# On_Board_Computer.net
KiCad netlist of a schematic drawn in EAGLE
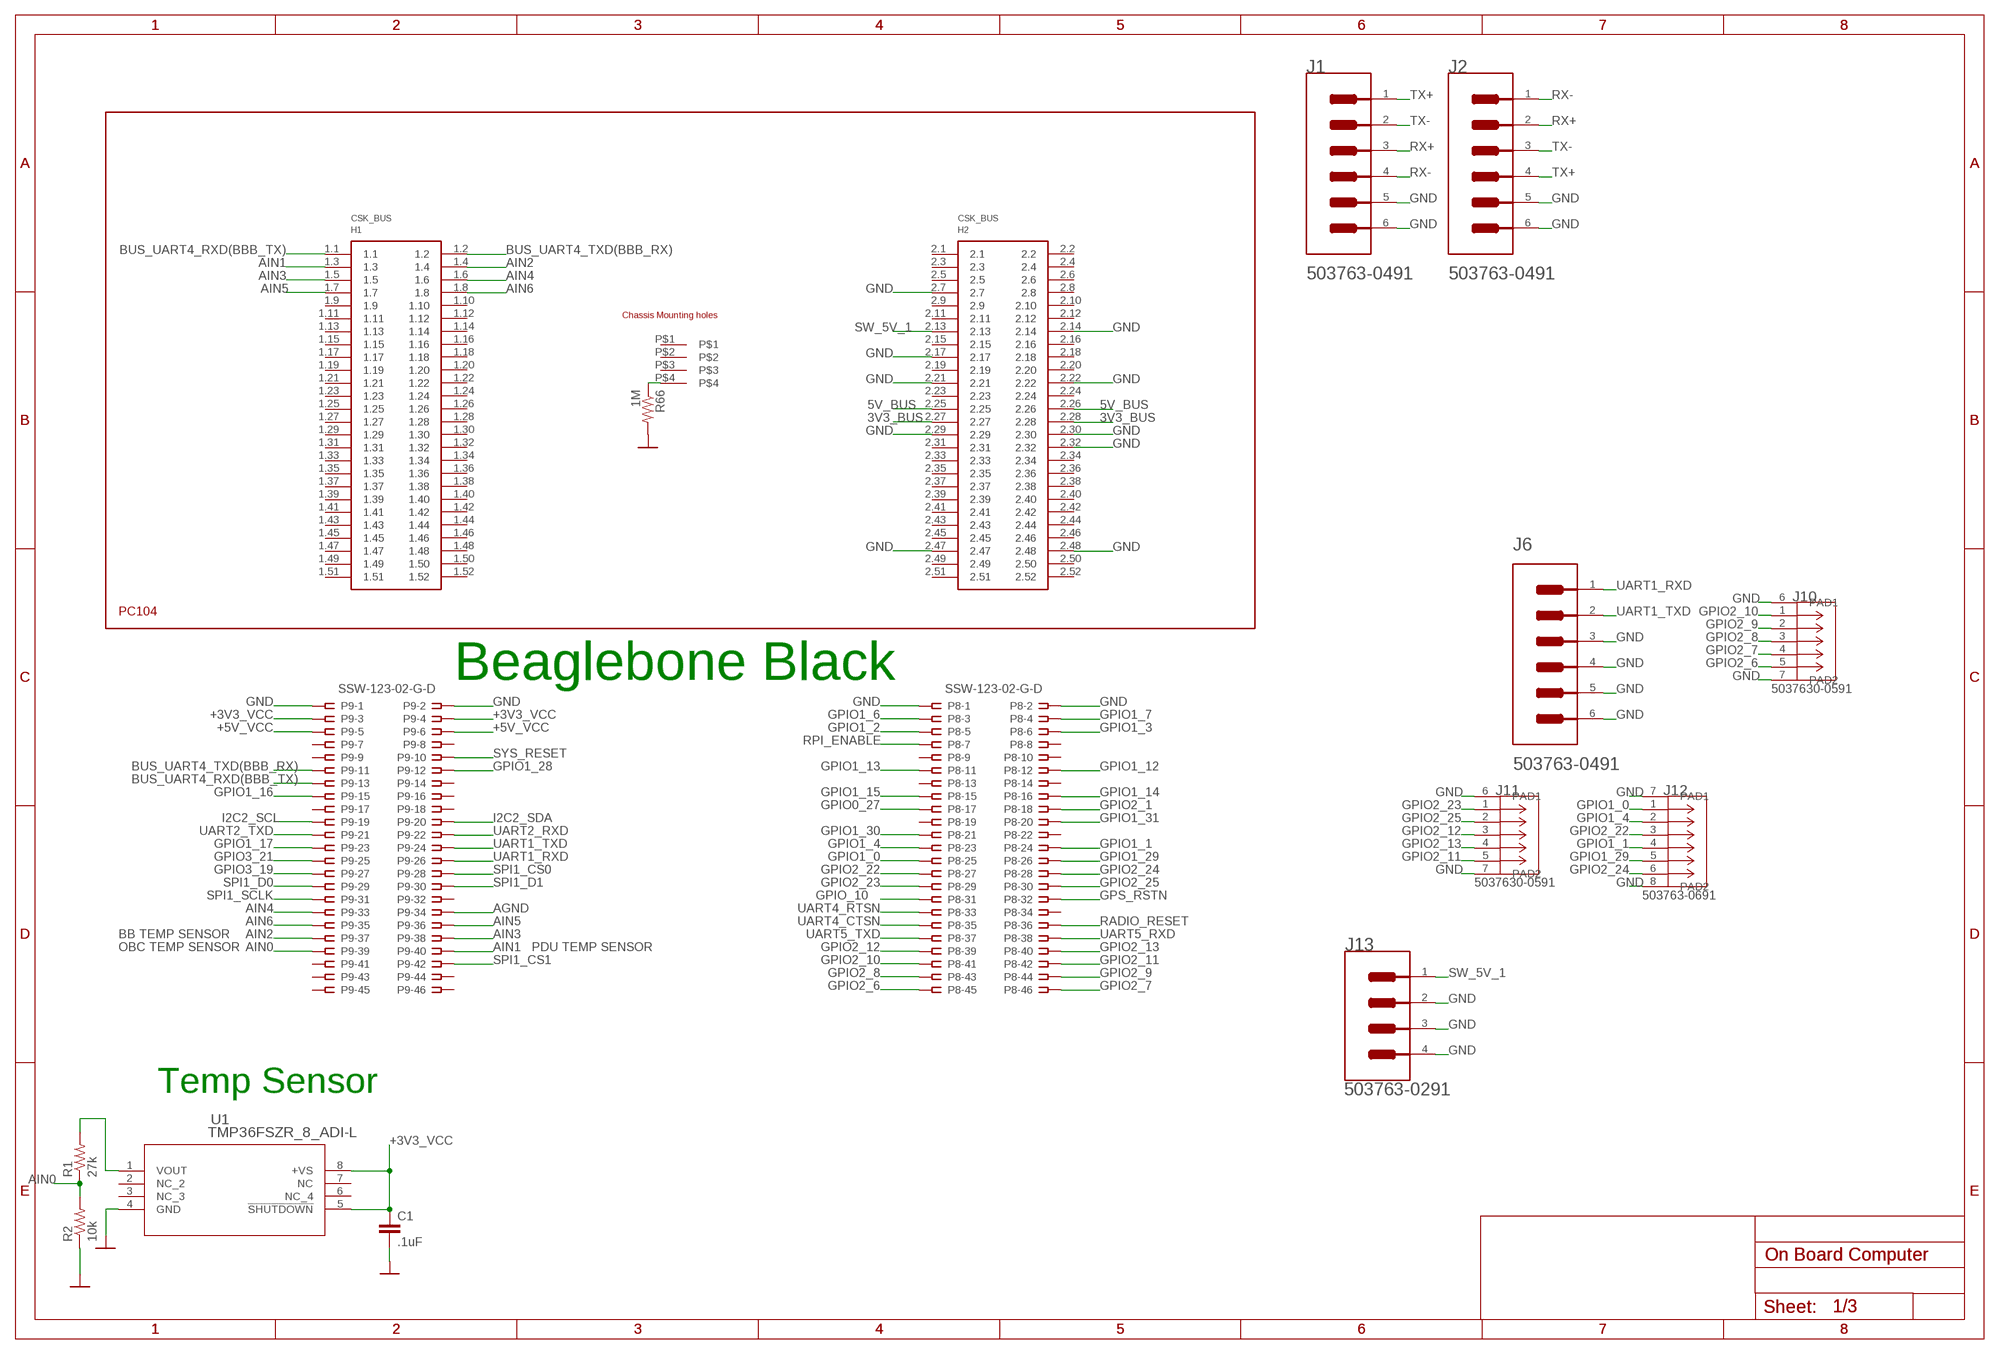
[diagram p0: schematic, sheet 1]
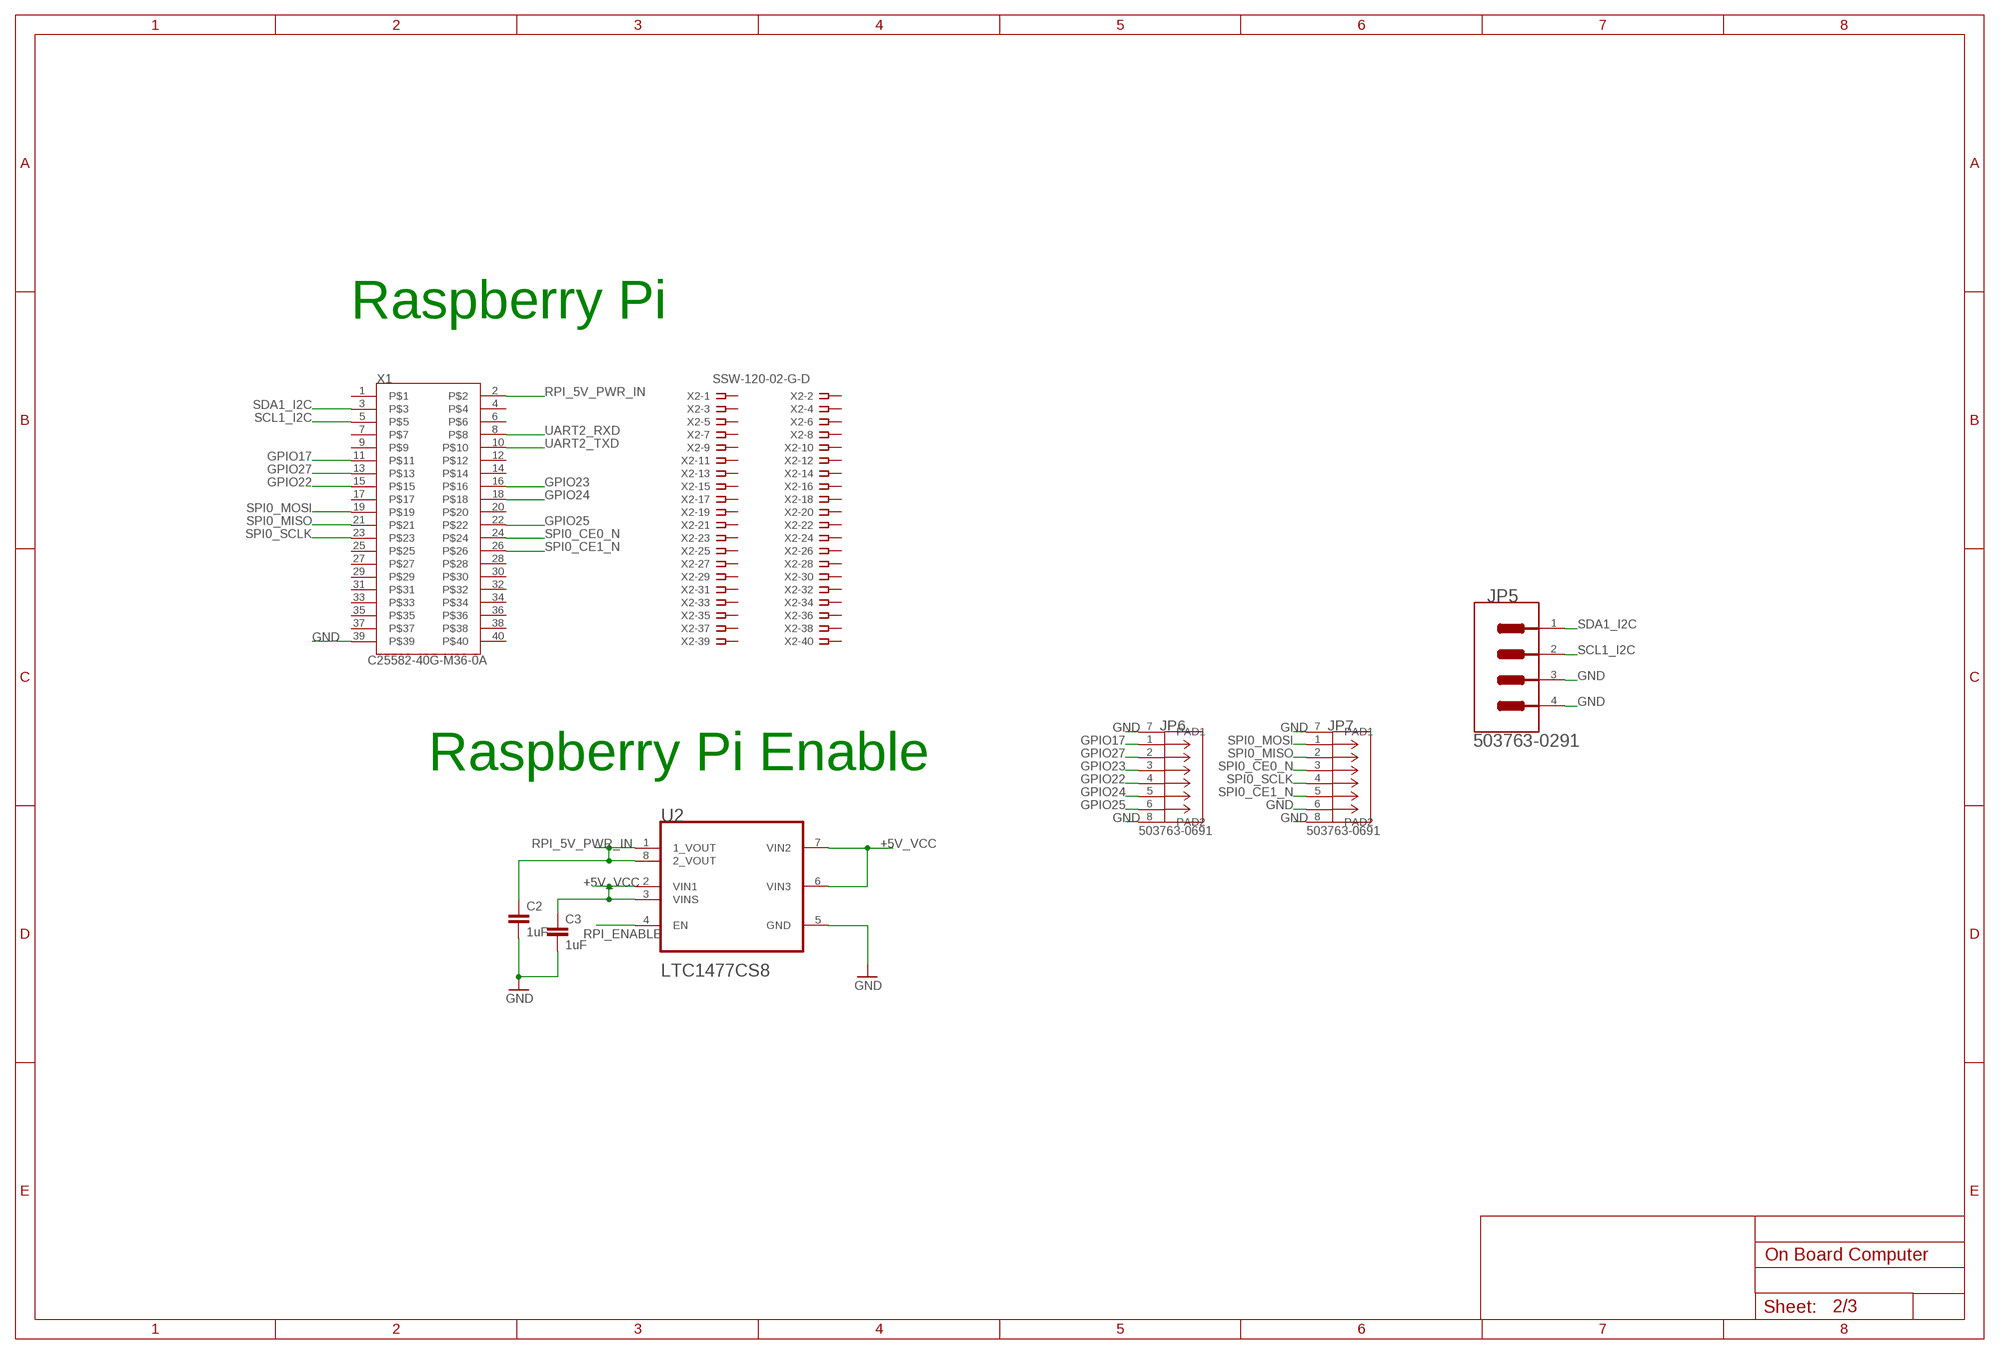
[diagram p1: schematic, sheet 2]
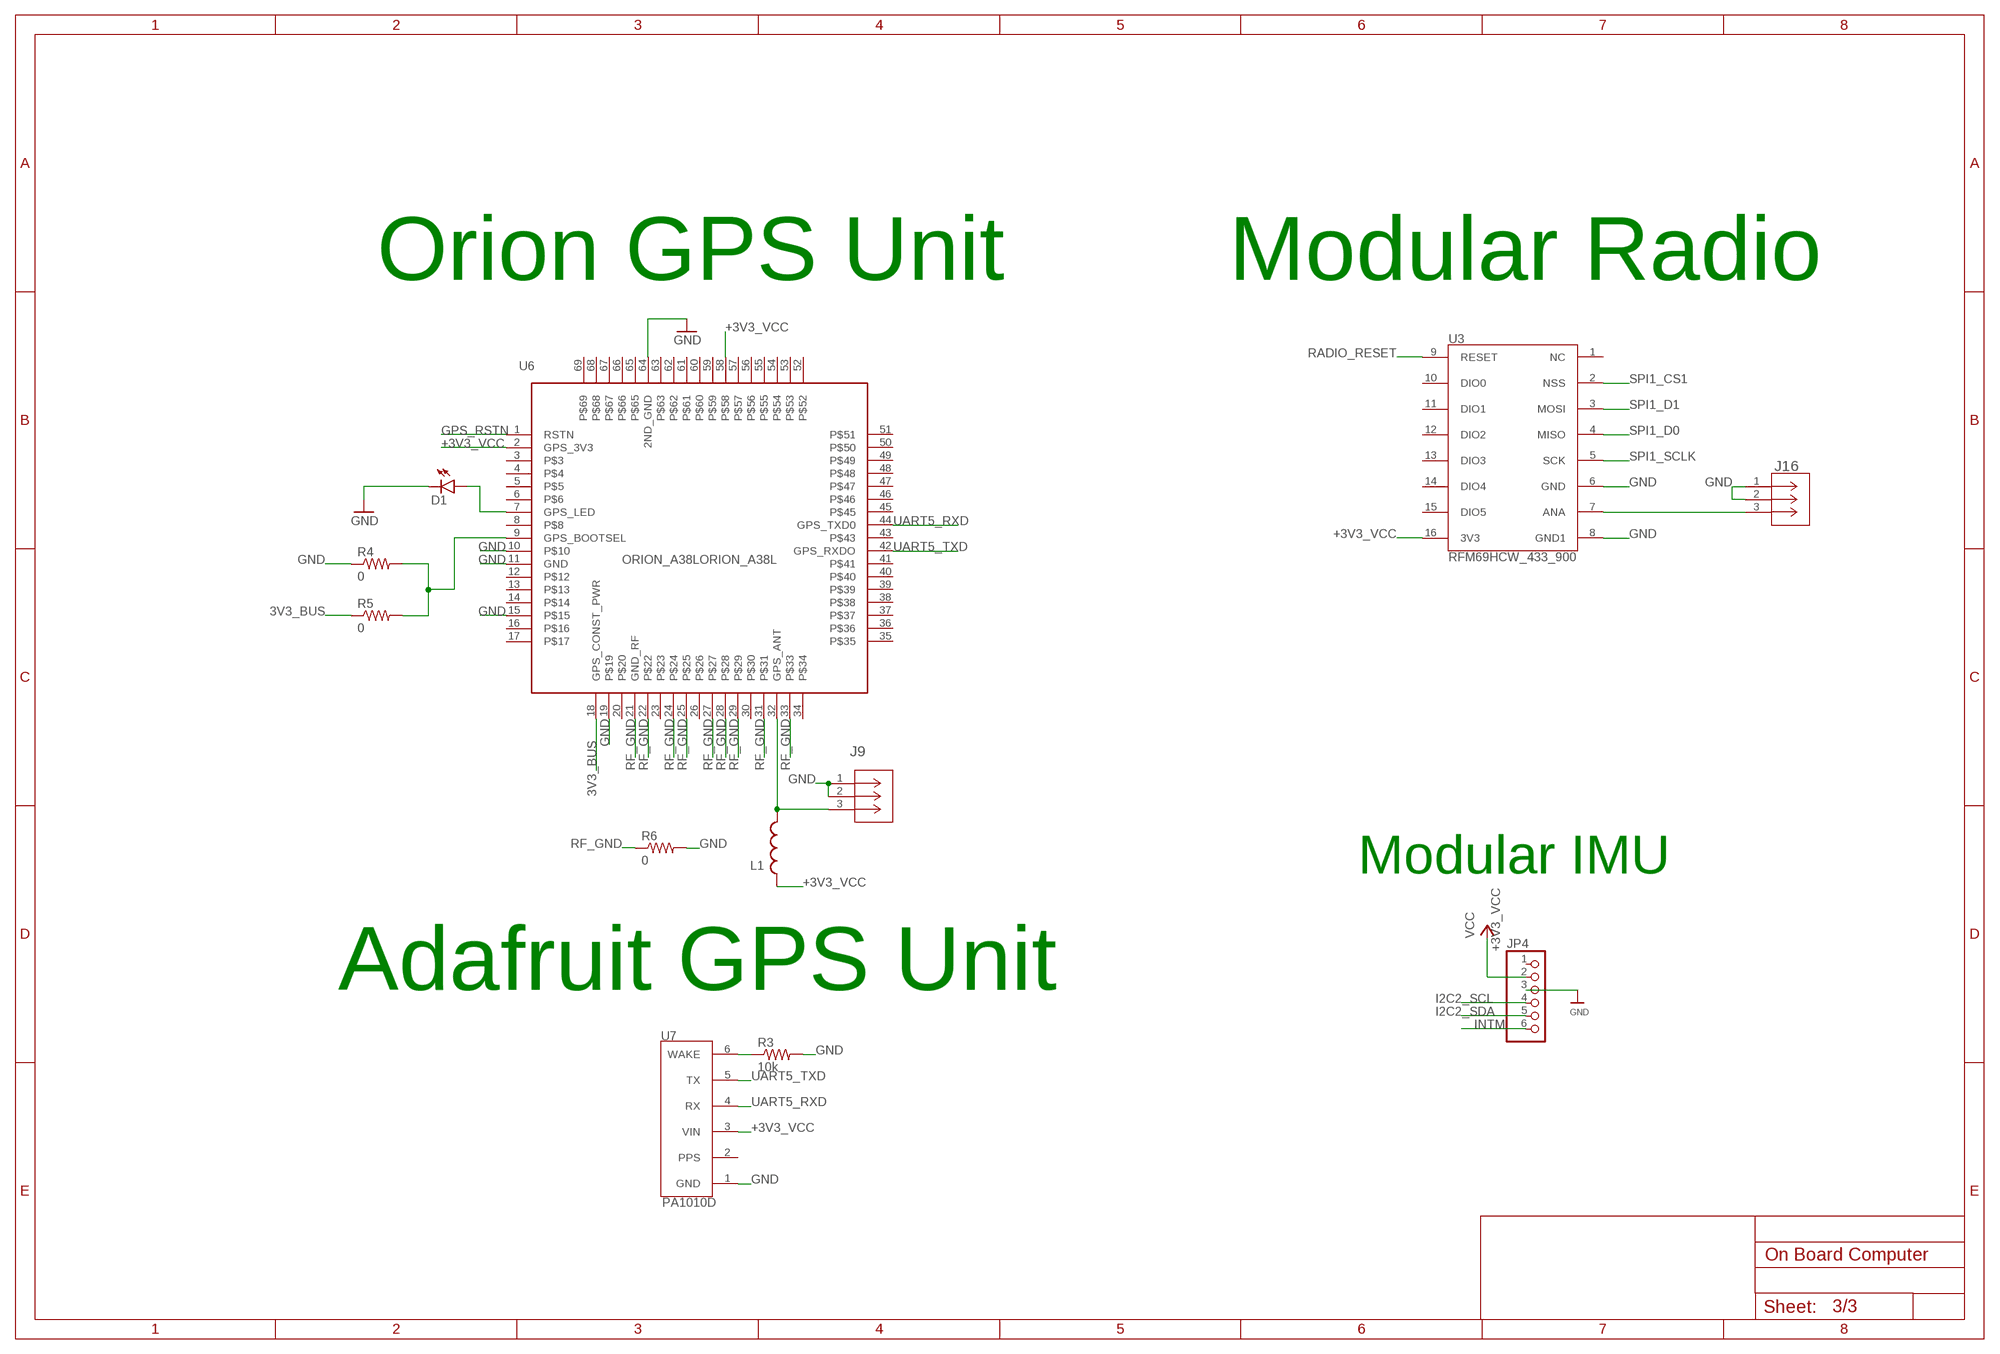
[diagram p2: schematic, sheet 3]

(export (version "E")
  (design (tool "Eeschema 10.0.6"))
  (components
    (comp (ref "D1")
      (value "LEDCHIP-LED0603")
      (footprint "eagle-import:CHIP-LED0603")
      (libsource (lib "eagle-import") (part "LEDCHIP-LED0603"))
    )
    (comp (ref "J9")
      (value "U.FL-R-SMT-1(01)")
      (footprint "eagle-import:CONN_-SMT-1(01)")
      (fields (field (name "COPYRIGHT") "Copyright (C) 2018 Accelerated Designs. All rights reserved"))
      (libsource (lib "eagle-import") (part "U.FL-R-SMT-1(01)"))
    )
    (comp (ref "J16")
      (value "U.FL-R-SMT-1(01)")
      (footprint "eagle-import:CONN_-SMT-1(01)")
      (fields (field (name "COPYRIGHT") "Copyright (C) 2018 Accelerated Designs. All rights reserved"))
      (libsource (lib "eagle-import") (part "U.FL-R-SMT-1(01)"))
    )
    (comp (ref "JP4")
      (value "HEADER-1X670MIL")
      (footprint "eagle-import:1X06_ROUND_70")
      (libsource (lib "eagle-import") (part "HEADER-1X670MIL"))
    )
    (comp (ref "L1")
      (value "L")
      (footprint "eagle-import:INDC2012X145N")
      (fields
        (field (name "DIGI-KEY_PART_NUMBER") "490-18463-1-ND")
        (field (name "MF") "Murata Electronics North America")
        (field (name "MP") "LQM21DH100M70L")
      )
      (libsource (lib "eagle-import") (part "L"))
    )
    (comp (ref "R3")
      (value "10k")
      (footprint "eagle-import:0805")
      (libsource (lib "eagle-import") (part "RESISTOR0805-RES"))
    )
    (comp (ref "R4")
      (value "0")
      (footprint "eagle-import:0805")
      (libsource (lib "eagle-import") (part "RESISTOR0805-RES"))
    )
    (comp (ref "R5")
      (value "0")
      (footprint "eagle-import:0805")
      (libsource (lib "eagle-import") (part "RESISTOR0805-RES"))
    )
    (comp (ref "R6")
      (value "0")
      (footprint "eagle-import:0805")
      (libsource (lib "eagle-import") (part "RESISTOR0805-RES"))
    )
    (comp (ref "U3")
      (value "RFM69HCW_433_900")
      (footprint "eagle-import:RFM69HCW_433")
      (libsource (lib "eagle-import") (part "RFM69HCW_433_900"))
    )
    (comp (ref "U6")
      (value "ORION_A38LORION_A38L")
      (footprint "eagle-import:ORION_A38L")
      (libsource (lib "eagle-import") (part "ORION_A38LORION_A38L"))
    )
    (comp (ref "U7")
      (value "PA1010D")
      (footprint "eagle-import:PA1010D")
      (libsource (lib "eagle-import") (part "PA1010D"))
    )
    (comp (ref "C2")
      (value "1uF")
      (footprint "eagle-import:0805")
      (libsource (lib "eagle-import") (part "CAP0805"))
    )
    (comp (ref "C3")
      (value "1uF")
      (footprint "eagle-import:0805")
      (libsource (lib "eagle-import") (part "CAP0805"))
    )
    (comp (ref "JP5")
      (value "MOLEX_503763-0291MOLEX_503763-0291_0_0")
      (footprint "eagle-import:MOLEX_503763-0291_0")
      (fields
        (field (name "DIGIKEY_PART_NUMBER") "WM10654CT-ND")
        (field (name "MF") "Molex")
        (field (name "MOUSER_PART_NUMBER") "538-503763-0291")
      )
      (libsource (lib "eagle-import") (part "MOLEX_503763-0291MOLEX_503763-0291_0_0"))
    )
    (comp (ref "JP6")
      (value "503763-0691")
      (footprint "eagle-import:CONN_503763-0691_MOL")
      (fields (field (name "COPYRIGHT") "Copyright (C) 2018 Accelerated Designs. All rights reserved"))
      (libsource (lib "eagle-import") (part "503763-0691"))
    )
    (comp (ref "JP7")
      (value "503763-0691")
      (footprint "eagle-import:CONN_503763-0691_MOL")
      (fields (field (name "COPYRIGHT") "Copyright (C) 2018 Accelerated Designs. All rights reserved"))
      (libsource (lib "eagle-import") (part "503763-0691"))
    )
    (comp (ref "U2")
      (value "LTC1477CS8LINEAR_TECHNOLOGY_LTC1477CS8_0_2")
      (footprint "eagle-import:LINEAR_TECHNOLOGY_LTC1477CS8_2")
      (fields (field (name "MF") "Linear Technology") (field (name "MPN") "LTC1477CS8"))
      (libsource (lib "eagle-import") (part "LTC1477CS8LINEAR_TECHNOLOGY_LTC1477CS8_0_2"))
    )
    (comp (ref "X1")
      (value "C25582-40G-M36-0A")
      (footprint "eagle-import:ADAFRUIT_C25582-40G-M36-0A_0")
      (libsource (lib "eagle-import") (part "C25582-40G-M36-0A"))
    )
    (comp (ref "X2")
      (value "SSW-120-02-G-D")
      (footprint "eagle-import:SSW-120-02-G-D")
      (fields (field (name "MF") "Samtec Inc."))
      (libsource (lib "eagle-import") (part "SSW-120-02-G-D"))
    )
    (comp (ref "C1")
      (value ".1uF")
      (footprint "eagle-import:0805")
      (libsource (lib "eagle-import") (part "CAP0805"))
    )
    (comp (ref "H1")
      (value "PC104_WCONN")
      (footprint "eagle-import:PC104_WCONN")
      (libsource (lib "eagle-import") (part "PC104_WCONN"))
    )
    (comp (ref "J1")
      (value "MOLEX_503763-0491MOLEX_503763-0491_0_0")
      (footprint "eagle-import:MOLEX_503763-0491_0")
      (fields
        (field (name "DIGIKEY_PART_NUMBER") "WM10655CT-ND")
        (field (name "MF") "Molex")
        (field (name "MOUSER_PART_NUMBER") "538-503763-0491")
      )
      (libsource (lib "eagle-import") (part "MOLEX_503763-0491MOLEX_503763-0491_0_0"))
    )
    (comp (ref "J2")
      (value "MOLEX_503763-0491MOLEX_503763-0491_0_0")
      (footprint "eagle-import:MOLEX_503763-0491_0")
      (fields
        (field (name "DIGIKEY_PART_NUMBER") "WM10655CT-ND")
        (field (name "MF") "Molex")
        (field (name "MOUSER_PART_NUMBER") "538-503763-0491")
      )
      (libsource (lib "eagle-import") (part "MOLEX_503763-0491MOLEX_503763-0491_0_0"))
    )
    (comp (ref "J6")
      (value "MOLEX_503763-0491MOLEX_503763-0491_0_0")
      (footprint "eagle-import:MOLEX_503763-0491_0")
      (fields
        (field (name "DIGIKEY_PART_NUMBER") "WM10655CT-ND")
        (field (name "MF") "Molex")
        (field (name "MOUSER_PART_NUMBER") "538-503763-0491")
      )
      (libsource (lib "eagle-import") (part "MOLEX_503763-0491MOLEX_503763-0491_0_0"))
    )
    (comp (ref "J10")
      (value "503763-0591")
      (footprint "eagle-import:CONN_5037630591_MOL")
      (fields (field (name "COPYRIGHT") "Copyright (C) 2018 Accelerated Designs. All rights reserved"))
      (libsource (lib "eagle-import") (part "503763-0591"))
    )
    (comp (ref "J11")
      (value "503763-0591")
      (footprint "eagle-import:CONN_5037630591_MOL")
      (fields (field (name "COPYRIGHT") "Copyright (C) 2018 Accelerated Designs. All rights reserved"))
      (libsource (lib "eagle-import") (part "503763-0591"))
    )
    (comp (ref "J12")
      (value "503763-0691")
      (footprint "eagle-import:CONN_503763-0691_MOL")
      (fields (field (name "COPYRIGHT") "Copyright (C) 2018 Accelerated Designs. All rights reserved"))
      (libsource (lib "eagle-import") (part "503763-0691"))
    )
    (comp (ref "J13")
      (value "MOLEX_503763-0291MOLEX_503763-0291_0_0")
      (footprint "eagle-import:MOLEX_503763-0291_0")
      (fields
        (field (name "DIGIKEY_PART_NUMBER") "WM10654CT-ND")
        (field (name "MF") "Molex")
        (field (name "MOUSER_PART_NUMBER") "538-503763-0291")
      )
      (libsource (lib "eagle-import") (part "MOLEX_503763-0291MOLEX_503763-0291_0_0"))
    )
    (comp (ref "P8")
      (value "SSW-123-02-G-D")
      (footprint "eagle-import:SSW-123-02-G-D")
      (fields (field (name "MF") "Samtec Inc."))
      (libsource (lib "eagle-import") (part "SSW-123-02-G-D"))
    )
    (comp (ref "P9")
      (value "SSW-123-02-G-D")
      (footprint "eagle-import:SSW-123-02-G-D")
      (fields (field (name "MF") "Samtec Inc."))
      (libsource (lib "eagle-import") (part "SSW-123-02-G-D"))
    )
    (comp (ref "R1")
      (value "27k")
      (footprint "eagle-import:0805")
      (libsource (lib "eagle-import") (part "RESISTOR0805-RES"))
    )
    (comp (ref "R2")
      (value "10k")
      (footprint "eagle-import:0805")
      (libsource (lib "eagle-import") (part "RESISTOR0805-RES"))
    )
    (comp (ref "R66")
      (value "1M")
      (footprint "eagle-import:0805")
      (libsource (lib "eagle-import") (part "RESISTOR0805-RES"))
    )
    (comp (ref "U1")
      (value "TMP36FSZR_8_ADI-L")
      (footprint "eagle-import:R_8_ADI-L")
      (fields
        (field (name "MANUFACTURER_PART_NUMBER") "TMP36FSZ")
        (field (name "COPYRIGHT") "Copyright (C) 2021 Ultra Librarian. All rights reserved.")
      )
      (libsource (lib "eagle-import") (part "TMP36FSZR_8_ADI-L"))
    )
  )
  (nets
    (net (code "1") (name "+3V3_VCC") (class "Default")
      (node (ref "C1") (pin "1") (pinfunction "1_1") (pintype "passive"))
      (node (ref "JP4") (pin "2") (pinfunction "2_2") (pintype "passive"))
      (node (ref "L1") (pin "1") (pinfunction "1_1") (pintype "passive"))
      (node (ref "P9") (pin "3") (pinfunction "1_3") (pintype "passive"))
      (node (ref "P9") (pin "4") (pinfunction "1_4") (pintype "passive"))
      (node (ref "U1") (pin "5") (pinfunction "~{SHUTDOWN}_5") (pintype "passive"))
      (node (ref "U1") (pin "8") (pinfunction "+VS_8") (pintype "power_in"))
      (node (ref "U3") (pin "16") (pinfunction "3V3_16") (pintype "bidirectional"))
      (node (ref "U6") (pin "2") (pinfunction "GPS_3V3_2") (pintype "bidirectional"))
      (node (ref "U6") (pin "58") (pinfunction "P$58_58") (pintype "bidirectional"))
      (node (ref "U7") (pin "3") (pinfunction "VIN_3") (pintype "bidirectional"))
    )
    (net (code "2") (name "+5V_VCC") (class "Default")
      (node (ref "C3") (pin "1") (pinfunction "1_1") (pintype "passive"))
      (node (ref "P9") (pin "5") (pinfunction "1_5") (pintype "passive"))
      (node (ref "P9") (pin "6") (pinfunction "1_6") (pintype "passive"))
      (node (ref "U2") (pin "2") (pinfunction "VIN1_2") (pintype "power_in"))
      (node (ref "U2") (pin "3") (pinfunction "VINS_3") (pintype "power_in"))
      (node (ref "U2") (pin "6") (pinfunction "VIN3_6") (pintype "power_in"))
      (node (ref "U2") (pin "7") (pinfunction "VIN2_7") (pintype "power_in"))
    )
    (net (code "3") (name "3V3_BUS") (class "Default")
      (node (ref "H1") (pin "2.27") (pinfunction "2.27_2.27") (pintype "bidirectional"))
      (node (ref "H1") (pin "2.28") (pinfunction "2.28_2.28") (pintype "bidirectional"))
      (node (ref "R5") (pin "1") (pinfunction "1_1") (pintype "passive"))
      (node (ref "U6") (pin "18") (pinfunction "GPS_CONST_PWR_18") (pintype "bidirectional"))
    )
    (net (code "4") (name "5V_BUS") (class "Default")
      (node (ref "H1") (pin "2.25") (pinfunction "2.25_2.25") (pintype "bidirectional"))
      (node (ref "H1") (pin "2.26") (pinfunction "2.26_2.26") (pintype "bidirectional"))
    )
    (net (code "5") (name "AGND") (class "Default")
      (node (ref "P9") (pin "34") (pinfunction "1_34") (pintype "passive"))
    )
    (net (code "6") (name "AIN0") (class "Default")
      (node (ref "P9") (pin "39") (pinfunction "1_39") (pintype "passive"))
      (node (ref "R1") (pin "1") (pinfunction "1_1") (pintype "passive"))
      (node (ref "R2") (pin "2") (pinfunction "2_2") (pintype "passive"))
    )
    (net (code "7") (name "AIN1") (class "Default")
      (node (ref "H1") (pin "1.3") (pinfunction "1.3_1.3") (pintype "bidirectional"))
      (node (ref "P9") (pin "40") (pinfunction "1_40") (pintype "passive"))
    )
    (net (code "8") (name "AIN2") (class "Default")
      (node (ref "H1") (pin "1.4") (pinfunction "1.4_1.4") (pintype "bidirectional"))
      (node (ref "P9") (pin "37") (pinfunction "1_37") (pintype "passive"))
    )
    (net (code "9") (name "AIN3") (class "Default")
      (node (ref "H1") (pin "1.5") (pinfunction "1.5_1.5") (pintype "bidirectional"))
      (node (ref "P9") (pin "38") (pinfunction "1_38") (pintype "passive"))
    )
    (net (code "10") (name "AIN4") (class "Default")
      (node (ref "H1") (pin "1.6") (pinfunction "1.6_1.6") (pintype "bidirectional"))
      (node (ref "P9") (pin "33") (pinfunction "1_33") (pintype "passive"))
    )
    (net (code "11") (name "AIN5") (class "Default")
      (node (ref "H1") (pin "1.7") (pinfunction "1.7_1.7") (pintype "bidirectional"))
      (node (ref "P9") (pin "36") (pinfunction "1_36") (pintype "passive"))
    )
    (net (code "12") (name "AIN6") (class "Default")
      (node (ref "H1") (pin "1.8") (pinfunction "1.8_1.8") (pintype "bidirectional"))
      (node (ref "P9") (pin "35") (pinfunction "1_35") (pintype "passive"))
    )
    (net (code "13") (name "BUS_UART4_RXD(BBB_TX)") (class "Default")
      (node (ref "H1") (pin "1.1") (pinfunction "1.1_1.1") (pintype "bidirectional"))
      (node (ref "P9") (pin "13") (pinfunction "1_13") (pintype "passive"))
    )
    (net (code "14") (name "BUS_UART4_TXD(BBB_RX)") (class "Default")
      (node (ref "H1") (pin "1.2") (pinfunction "1.2_1.2") (pintype "bidirectional"))
      (node (ref "P9") (pin "11") (pinfunction "1_11") (pintype "passive"))
    )
    (net (code "15") (name "GND") (class "Default")
      (node (ref "C1") (pin "2") (pinfunction "2_2") (pintype "passive"))
      (node (ref "C2") (pin "2") (pinfunction "2_2") (pintype "passive"))
      (node (ref "C3") (pin "2") (pinfunction "2_2") (pintype "passive"))
      (node (ref "D1") (pin "C") (pinfunction "C_C") (pintype "passive"))
      (node (ref "H1") (pin "2.14") (pinfunction "2.14_2.14") (pintype "bidirectional"))
      (node (ref "H1") (pin "2.17") (pinfunction "2.17_2.17") (pintype "bidirectional"))
      (node (ref "H1") (pin "2.21") (pinfunction "2.21_2.21") (pintype "bidirectional"))
      (node (ref "H1") (pin "2.22") (pinfunction "2.22_2.22") (pintype "bidirectional"))
      (node (ref "H1") (pin "2.29") (pinfunction "2.29_2.29") (pintype "bidirectional"))
      (node (ref "H1") (pin "2.30") (pinfunction "2.30_2.30") (pintype "bidirectional"))
      (node (ref "H1") (pin "2.32") (pinfunction "2.32_2.32") (pintype "bidirectional"))
      (node (ref "H1") (pin "2.47") (pinfunction "2.47_2.47") (pintype "bidirectional"))
      (node (ref "H1") (pin "2.48") (pinfunction "2.48_2.48") (pintype "bidirectional"))
      (node (ref "H1") (pin "2.7") (pinfunction "2.7_2.7") (pintype "bidirectional"))
      (node (ref "J1") (pin "5") (pinfunction "MNT_1_5") (pintype "passive"))
      (node (ref "J1") (pin "6") (pinfunction "MNT_2_6") (pintype "passive"))
      (node (ref "J10") (pin "6") (pinfunction "PAD1_6") (pintype "bidirectional"))
      (node (ref "J10") (pin "7") (pinfunction "PAD2_7") (pintype "bidirectional"))
      (node (ref "J11") (pin "6") (pinfunction "PAD1_6") (pintype "bidirectional"))
      (node (ref "J11") (pin "7") (pinfunction "PAD2_7") (pintype "bidirectional"))
      (node (ref "J12") (pin "7") (pinfunction "PAD1_7") (pintype "bidirectional"))
      (node (ref "J12") (pin "8") (pinfunction "PAD2_8") (pintype "bidirectional"))
      (node (ref "J13") (pin "2") (pinfunction "2_2") (pintype "bidirectional"))
      (node (ref "J13") (pin "3") (pinfunction "MNT_1_3") (pintype "bidirectional"))
      (node (ref "J13") (pin "4") (pinfunction "MNT_2_4") (pintype "bidirectional"))
      (node (ref "J16") (pin "1") (pinfunction "1_1") (pintype "passive"))
      (node (ref "J16") (pin "2") (pinfunction "2_2") (pintype "passive"))
      (node (ref "J2") (pin "5") (pinfunction "MNT_1_5") (pintype "passive"))
      (node (ref "J2") (pin "6") (pinfunction "MNT_2_6") (pintype "passive"))
      (node (ref "J6") (pin "3") (pinfunction "3_3") (pintype "passive"))
      (node (ref "J6") (pin "4") (pinfunction "4_4") (pintype "passive"))
      (node (ref "J6") (pin "5") (pinfunction "MNT_1_5") (pintype "passive"))
      (node (ref "J6") (pin "6") (pinfunction "MNT_2_6") (pintype "passive"))
      (node (ref "J9") (pin "1") (pinfunction "1_1") (pintype "passive"))
      (node (ref "J9") (pin "2") (pinfunction "2_2") (pintype "passive"))
      (node (ref "JP4") (pin "3") (pinfunction "3_3") (pintype "passive"))
      (node (ref "JP5") (pin "3") (pinfunction "MNT_1_3") (pintype "bidirectional"))
      (node (ref "JP5") (pin "4") (pinfunction "MNT_2_4") (pintype "bidirectional"))
      (node (ref "JP6") (pin "7") (pinfunction "PAD1_7") (pintype "bidirectional"))
      (node (ref "JP6") (pin "8") (pinfunction "PAD2_8") (pintype "bidirectional"))
      (node (ref "JP7") (pin "6") (pinfunction "6_6") (pintype "passive"))
      (node (ref "JP7") (pin "7") (pinfunction "PAD1_7") (pintype "bidirectional"))
      (node (ref "JP7") (pin "8") (pinfunction "PAD2_8") (pintype "bidirectional"))
      (node (ref "P8") (pin "1") (pinfunction "1_1") (pintype "passive"))
      (node (ref "P8") (pin "2") (pinfunction "1_2") (pintype "passive"))
      (node (ref "P9") (pin "1") (pinfunction "1_1") (pintype "passive"))
      (node (ref "P9") (pin "2") (pinfunction "1_2") (pintype "passive"))
      (node (ref "R2") (pin "1") (pinfunction "1_1") (pintype "passive"))
      (node (ref "R3") (pin "2") (pinfunction "2_2") (pintype "passive"))
      (node (ref "R4") (pin "1") (pinfunction "1_1") (pintype "passive"))
      (node (ref "R6") (pin "2") (pinfunction "2_2") (pintype "passive"))
      (node (ref "R66") (pin "2") (pinfunction "2_2") (pintype "passive"))
      (node (ref "U1") (pin "4") (pinfunction "GND_4") (pintype "passive"))
      (node (ref "U2") (pin "5") (pinfunction "GND_5") (pintype "power_in"))
      (node (ref "U3") (pin "6") (pinfunction "GND_6") (pintype "bidirectional"))
      (node (ref "U3") (pin "8") (pinfunction "GND1_8") (pintype "bidirectional"))
      (node (ref "U6") (pin "10") (pinfunction "P$10_10") (pintype "bidirectional"))
      (node (ref "U6") (pin "11") (pinfunction "GND_11") (pintype "bidirectional"))
      (node (ref "U6") (pin "15") (pinfunction "P$15_15") (pintype "bidirectional"))
      (node (ref "U6") (pin "19") (pinfunction "P$19_19") (pintype "bidirectional"))
      (node (ref "U6") (pin "64") (pinfunction "2ND_GND_64") (pintype "bidirectional"))
      (node (ref "U7") (pin "1") (pinfunction "GND_1") (pintype "bidirectional"))
      (node (ref "X1") (pin "39") (pinfunction "P$39_39") (pintype "bidirectional"))
    )
    (net (code "16") (name "GPIO0_27") (class "Default")
      (node (ref "P8") (pin "17") (pinfunction "1_17") (pintype "passive"))
    )
    (net (code "17") (name "GPIO1_0") (class "Default")
      (node (ref "J12") (pin "1") (pinfunction "1_1") (pintype "passive"))
      (node (ref "P8") (pin "25") (pinfunction "1_25") (pintype "passive"))
    )
    (net (code "18") (name "GPIO1_1") (class "Default")
      (node (ref "J12") (pin "4") (pinfunction "4_4") (pintype "passive"))
      (node (ref "P8") (pin "24") (pinfunction "1_24") (pintype "passive"))
    )
    (net (code "19") (name "GPIO1_2") (class "Default")
      (node (ref "P8") (pin "5") (pinfunction "1_5") (pintype "passive"))
    )
    (net (code "20") (name "GPIO1_3") (class "Default")
      (node (ref "P8") (pin "6") (pinfunction "1_6") (pintype "passive"))
    )
    (net (code "21") (name "GPIO1_4") (class "Default")
      (node (ref "J12") (pin "2") (pinfunction "2_2") (pintype "passive"))
      (node (ref "P8") (pin "23") (pinfunction "1_23") (pintype "passive"))
    )
    (net (code "22") (name "GPIO1_6") (class "Default")
      (node (ref "P8") (pin "3") (pinfunction "1_3") (pintype "passive"))
    )
    (net (code "23") (name "GPIO1_7") (class "Default")
      (node (ref "P8") (pin "4") (pinfunction "1_4") (pintype "passive"))
    )
    (net (code "24") (name "GPIO1_12") (class "Default")
      (node (ref "P8") (pin "12") (pinfunction "1_12") (pintype "passive"))
    )
    (net (code "25") (name "GPIO1_13") (class "Default")
      (node (ref "P8") (pin "11") (pinfunction "1_11") (pintype "passive"))
    )
    (net (code "26") (name "GPIO1_14") (class "Default")
      (node (ref "P8") (pin "16") (pinfunction "1_16") (pintype "passive"))
    )
    (net (code "27") (name "GPIO1_15") (class "Default")
      (node (ref "P8") (pin "15") (pinfunction "1_15") (pintype "passive"))
    )
    (net (code "28") (name "GPIO1_16") (class "Default")
      (node (ref "P9") (pin "15") (pinfunction "1_15") (pintype "passive"))
    )
    (net (code "29") (name "GPIO1_17") (class "Default")
      (node (ref "P9") (pin "23") (pinfunction "1_23") (pintype "passive"))
    )
    (net (code "30") (name "GPIO1_28") (class "Default")
      (node (ref "P9") (pin "12") (pinfunction "1_12") (pintype "passive"))
    )
    (net (code "31") (name "GPIO1_29") (class "Default")
      (node (ref "J12") (pin "5") (pinfunction "5_5") (pintype "passive"))
      (node (ref "P8") (pin "26") (pinfunction "1_26") (pintype "passive"))
    )
    (net (code "32") (name "GPIO1_30") (class "Default")
      (node (ref "P8") (pin "21") (pinfunction "1_21") (pintype "passive"))
    )
    (net (code "33") (name "GPIO1_31") (class "Default")
      (node (ref "P8") (pin "20") (pinfunction "1_20") (pintype "passive"))
    )
    (net (code "34") (name "GPIO2_1") (class "Default")
      (node (ref "P8") (pin "18") (pinfunction "1_18") (pintype "passive"))
    )
    (net (code "35") (name "GPIO2_6") (class "Default")
      (node (ref "J10") (pin "5") (pinfunction "5_5") (pintype "passive"))
      (node (ref "P8") (pin "45") (pinfunction "1_45") (pintype "passive"))
    )
    (net (code "36") (name "GPIO2_7") (class "Default")
      (node (ref "J10") (pin "4") (pinfunction "4_4") (pintype "passive"))
      (node (ref "P8") (pin "46") (pinfunction "1_46") (pintype "passive"))
    )
    (net (code "37") (name "GPIO2_8") (class "Default")
      (node (ref "J10") (pin "3") (pinfunction "3_3") (pintype "passive"))
      (node (ref "P8") (pin "43") (pinfunction "1_43") (pintype "passive"))
    )
    (net (code "38") (name "GPIO2_9") (class "Default")
      (node (ref "J10") (pin "2") (pinfunction "2_2") (pintype "passive"))
      (node (ref "P8") (pin "44") (pinfunction "1_44") (pintype "passive"))
    )
    (net (code "39") (name "GPIO2_10") (class "Default")
      (node (ref "J10") (pin "1") (pinfunction "1_1") (pintype "passive"))
      (node (ref "P8") (pin "41") (pinfunction "1_41") (pintype "passive"))
    )
    (net (code "40") (name "GPIO2_11") (class "Default")
      (node (ref "J11") (pin "5") (pinfunction "5_5") (pintype "passive"))
      (node (ref "P8") (pin "42") (pinfunction "1_42") (pintype "passive"))
    )
    (net (code "41") (name "GPIO2_12") (class "Default")
      (node (ref "J11") (pin "3") (pinfunction "3_3") (pintype "passive"))
      (node (ref "P8") (pin "39") (pinfunction "1_39") (pintype "passive"))
    )
    (net (code "42") (name "GPIO2_13") (class "Default")
      (node (ref "J11") (pin "4") (pinfunction "4_4") (pintype "passive"))
      (node (ref "P8") (pin "40") (pinfunction "1_40") (pintype "passive"))
    )
    (net (code "43") (name "GPIO2_22") (class "Default")
      (node (ref "J12") (pin "3") (pinfunction "3_3") (pintype "passive"))
      (node (ref "P8") (pin "27") (pinfunction "1_27") (pintype "passive"))
    )
    (net (code "44") (name "GPIO2_23") (class "Default")
      (node (ref "J11") (pin "1") (pinfunction "1_1") (pintype "passive"))
      (node (ref "P8") (pin "29") (pinfunction "1_29") (pintype "passive"))
    )
    (net (code "45") (name "GPIO2_24") (class "Default")
      (node (ref "J12") (pin "6") (pinfunction "6_6") (pintype "passive"))
      (node (ref "P8") (pin "28") (pinfunction "1_28") (pintype "passive"))
    )
    (net (code "46") (name "GPIO2_25") (class "Default")
      (node (ref "J11") (pin "2") (pinfunction "2_2") (pintype "passive"))
      (node (ref "P8") (pin "30") (pinfunction "1_30") (pintype "passive"))
    )
    (net (code "47") (name "GPIO3_19") (class "Default")
      (node (ref "P9") (pin "27") (pinfunction "1_27") (pintype "passive"))
    )
    (net (code "48") (name "GPIO3_21") (class "Default")
      (node (ref "P9") (pin "25") (pinfunction "1_25") (pintype "passive"))
    )
    (net (code "49") (name "GPIO17") (class "Default")
      (node (ref "JP6") (pin "1") (pinfunction "1_1") (pintype "passive"))
      (node (ref "X1") (pin "11") (pinfunction "P$11_11") (pintype "bidirectional"))
    )
    (net (code "50") (name "GPIO22") (class "Default")
      (node (ref "JP6") (pin "4") (pinfunction "4_4") (pintype "passive"))
      (node (ref "X1") (pin "15") (pinfunction "P$15_15") (pintype "bidirectional"))
    )
    (net (code "51") (name "GPIO23") (class "Default")
      (node (ref "JP6") (pin "3") (pinfunction "3_3") (pintype "passive"))
      (node (ref "X1") (pin "16") (pinfunction "P$16_16") (pintype "bidirectional"))
    )
    (net (code "52") (name "GPIO24") (class "Default")
      (node (ref "JP6") (pin "5") (pinfunction "5_5") (pintype "passive"))
      (node (ref "X1") (pin "18") (pinfunction "P$18_18") (pintype "bidirectional"))
    )
    (net (code "53") (name "GPIO25") (class "Default")
      (node (ref "JP6") (pin "6") (pinfunction "6_6") (pintype "passive"))
      (node (ref "X1") (pin "22") (pinfunction "P$22_22") (pintype "bidirectional"))
    )
    (net (code "54") (name "GPIO27") (class "Default")
      (node (ref "JP6") (pin "2") (pinfunction "2_2") (pintype "passive"))
      (node (ref "X1") (pin "13") (pinfunction "P$13_13") (pintype "bidirectional"))
    )
    (net (code "55") (name "GPIO_10") (class "Default")
      (node (ref "P8") (pin "31") (pinfunction "1_31") (pintype "passive"))
    )
    (net (code "56") (name "GPS_RSTN") (class "Default")
      (node (ref "P8") (pin "32") (pinfunction "1_32") (pintype "passive"))
      (node (ref "U6") (pin "1") (pinfunction "RSTN_1") (pintype "bidirectional"))
    )
    (net (code "57") (name "I2C2_SCL") (class "Default")
      (node (ref "JP4") (pin "4") (pinfunction "4_4") (pintype "passive"))
      (node (ref "P9") (pin "19") (pinfunction "1_19") (pintype "passive"))
    )
    (net (code "58") (name "I2C2_SDA") (class "Default")
      (node (ref "JP4") (pin "5") (pinfunction "5_5") (pintype "passive"))
      (node (ref "P9") (pin "20") (pinfunction "1_20") (pintype "passive"))
    )
    (net (code "59") (name "INTM") (class "Default")
      (node (ref "JP4") (pin "6") (pinfunction "6_6") (pintype "passive"))
    )
    (net (code "60") (name "Net-(H1-PadP$4)") (class "Default")
      (node (ref "H1") (pin "P$4") (pinfunction "P$4_P$4") (pintype "bidirectional"))
      (node (ref "R66") (pin "1") (pinfunction "1_1") (pintype "passive"))
    )
    (net (code "61") (name "Net-(U1-VOUT)") (class "Default")
      (node (ref "R1") (pin "2") (pinfunction "2_2") (pintype "passive"))
      (node (ref "U1") (pin "1") (pinfunction "VOUT_1") (pintype "output"))
    )
    (net (code "62") (name "Net-(U3-ANA)") (class "Default")
      (node (ref "J16") (pin "3") (pinfunction "3_3") (pintype "passive"))
      (node (ref "U3") (pin "7") (pinfunction "ANA_7") (pintype "bidirectional"))
    )
    (net (code "63") (name "Net-(U6-GPS_ANT)") (class "Default")
      (node (ref "J9") (pin "3") (pinfunction "3_3") (pintype "passive"))
      (node (ref "L1") (pin "2") (pinfunction "2_2") (pintype "passive"))
      (node (ref "U6") (pin "32") (pinfunction "GPS_ANT_32") (pintype "bidirectional"))
    )
    (net (code "64") (name "Net-(U6-GPS_BOOTSEL)") (class "Default")
      (node (ref "R4") (pin "2") (pinfunction "2_2") (pintype "passive"))
      (node (ref "R5") (pin "2") (pinfunction "2_2") (pintype "passive"))
      (node (ref "U6") (pin "9") (pinfunction "GPS_BOOTSEL_9") (pintype "bidirectional"))
    )
    (net (code "65") (name "Net-(U6-GPS_LED)") (class "Default")
      (node (ref "D1") (pin "A") (pinfunction "A_A") (pintype "passive"))
      (node (ref "U6") (pin "7") (pinfunction "GPS_LED_7") (pintype "bidirectional"))
    )
    (net (code "66") (name "Net-(U7-WAKE)") (class "Default")
      (node (ref "R3") (pin "1") (pinfunction "1_1") (pintype "passive"))
      (node (ref "U7") (pin "6") (pinfunction "WAKE_6") (pintype "bidirectional"))
    )
    (net (code "67") (name "RADIO_RESET") (class "Default")
      (node (ref "P8") (pin "36") (pinfunction "1_36") (pintype "passive"))
      (node (ref "U3") (pin "9") (pinfunction "RESET_9") (pintype "bidirectional"))
    )
    (net (code "68") (name "RF_GND") (class "Default")
      (node (ref "R6") (pin "1") (pinfunction "1_1") (pintype "passive"))
      (node (ref "U6") (pin "21") (pinfunction "GND_RF_21") (pintype "bidirectional"))
      (node (ref "U6") (pin "22") (pinfunction "P$22_22") (pintype "bidirectional"))
      (node (ref "U6") (pin "24") (pinfunction "P$24_24") (pintype "bidirectional"))
      (node (ref "U6") (pin "25") (pinfunction "P$25_25") (pintype "bidirectional"))
      (node (ref "U6") (pin "27") (pinfunction "P$27_27") (pintype "bidirectional"))
      (node (ref "U6") (pin "28") (pinfunction "P$28_28") (pintype "bidirectional"))
      (node (ref "U6") (pin "29") (pinfunction "P$29_29") (pintype "bidirectional"))
      (node (ref "U6") (pin "31") (pinfunction "P$31_31") (pintype "bidirectional"))
      (node (ref "U6") (pin "33") (pinfunction "P$33_33") (pintype "bidirectional"))
    )
    (net (code "69") (name "RPI_5V_PWR_IN") (class "Default")
      (node (ref "C2") (pin "1") (pinfunction "1_1") (pintype "passive"))
      (node (ref "U2") (pin "1") (pinfunction "1_VOUT_1") (pintype "power_in"))
      (node (ref "U2") (pin "8") (pinfunction "2_VOUT_8") (pintype "power_in"))
      (node (ref "X1") (pin "2") (pinfunction "P$2_2") (pintype "bidirectional"))
    )
    (net (code "70") (name "RPI_ENABLE") (class "Default")
      (node (ref "P8") (pin "7") (pinfunction "1_7") (pintype "passive"))
      (node (ref "U2") (pin "4") (pinfunction "EN_4") (pintype "input"))
    )
    (net (code "71") (name "RX+") (class "Default")
      (node (ref "J1") (pin "3") (pinfunction "3_3") (pintype "passive"))
      (node (ref "J2") (pin "2") (pinfunction "2_2") (pintype "passive"))
    )
    (net (code "72") (name "RX-") (class "Default")
      (node (ref "J1") (pin "4") (pinfunction "4_4") (pintype "passive"))
      (node (ref "J2") (pin "1") (pinfunction "1_1") (pintype "passive"))
    )
    (net (code "73") (name "SCL1_I2C") (class "Default")
      (node (ref "JP5") (pin "2") (pinfunction "2_2") (pintype "bidirectional"))
      (node (ref "X1") (pin "5") (pinfunction "P$5_5") (pintype "bidirectional"))
    )
    (net (code "74") (name "SDA1_I2C") (class "Default")
      (node (ref "JP5") (pin "1") (pinfunction "1_1") (pintype "bidirectional"))
      (node (ref "X1") (pin "3") (pinfunction "P$3_3") (pintype "bidirectional"))
    )
    (net (code "75") (name "SPI0_CE0_N") (class "Default")
      (node (ref "JP7") (pin "3") (pinfunction "3_3") (pintype "passive"))
      (node (ref "X1") (pin "24") (pinfunction "P$24_24") (pintype "bidirectional"))
    )
    (net (code "76") (name "SPI0_CE1_N") (class "Default")
      (node (ref "JP7") (pin "5") (pinfunction "5_5") (pintype "passive"))
      (node (ref "X1") (pin "26") (pinfunction "P$26_26") (pintype "bidirectional"))
    )
    (net (code "77") (name "SPI0_MISO") (class "Default")
      (node (ref "JP7") (pin "2") (pinfunction "2_2") (pintype "passive"))
      (node (ref "X1") (pin "21") (pinfunction "P$21_21") (pintype "bidirectional"))
    )
    (net (code "78") (name "SPI0_MOSI") (class "Default")
      (node (ref "JP7") (pin "1") (pinfunction "1_1") (pintype "passive"))
      (node (ref "X1") (pin "19") (pinfunction "P$19_19") (pintype "bidirectional"))
    )
    (net (code "79") (name "SPI0_SCLK") (class "Default")
      (node (ref "JP7") (pin "4") (pinfunction "4_4") (pintype "passive"))
      (node (ref "X1") (pin "23") (pinfunction "P$23_23") (pintype "bidirectional"))
    )
    (net (code "80") (name "SPI1_CS0") (class "Default")
      (node (ref "P9") (pin "28") (pinfunction "1_28") (pintype "passive"))
    )
    (net (code "81") (name "SPI1_CS1") (class "Default")
      (node (ref "P9") (pin "42") (pinfunction "1_42") (pintype "passive"))
      (node (ref "U3") (pin "2") (pinfunction "NSS_2") (pintype "bidirectional"))
    )
    (net (code "82") (name "SPI1_D0") (class "Default")
      (node (ref "P9") (pin "29") (pinfunction "1_29") (pintype "passive"))
      (node (ref "U3") (pin "4") (pinfunction "MISO_4") (pintype "bidirectional"))
    )
    (net (code "83") (name "SPI1_D1") (class "Default")
      (node (ref "P9") (pin "30") (pinfunction "1_30") (pintype "passive"))
      (node (ref "U3") (pin "3") (pinfunction "MOSI_3") (pintype "bidirectional"))
    )
    (net (code "84") (name "SPI1_SCLK") (class "Default")
      (node (ref "P9") (pin "31") (pinfunction "1_31") (pintype "passive"))
      (node (ref "U3") (pin "5") (pinfunction "SCK_5") (pintype "bidirectional"))
    )
    (net (code "85") (name "SW_5V_1") (class "Default")
      (node (ref "H1") (pin "2.13") (pinfunction "2.13_2.13") (pintype "bidirectional"))
      (node (ref "J13") (pin "1") (pinfunction "1_1") (pintype "bidirectional"))
    )
    (net (code "86") (name "SYS_RESET") (class "Default")
      (node (ref "P9") (pin "10") (pinfunction "1_10") (pintype "passive"))
    )
    (net (code "87") (name "TX+") (class "Default")
      (node (ref "J1") (pin "1") (pinfunction "1_1") (pintype "passive"))
      (node (ref "J2") (pin "4") (pinfunction "4_4") (pintype "passive"))
    )
    (net (code "88") (name "TX-") (class "Default")
      (node (ref "J1") (pin "2") (pinfunction "2_2") (pintype "passive"))
      (node (ref "J2") (pin "3") (pinfunction "3_3") (pintype "passive"))
    )
    (net (code "89") (name "UART1_RXD") (class "Default")
      (node (ref "J6") (pin "1") (pinfunction "1_1") (pintype "passive"))
      (node (ref "P9") (pin "26") (pinfunction "1_26") (pintype "passive"))
    )
    (net (code "90") (name "UART1_TXD") (class "Default")
      (node (ref "J6") (pin "2") (pinfunction "2_2") (pintype "passive"))
      (node (ref "P9") (pin "24") (pinfunction "1_24") (pintype "passive"))
    )
    (net (code "91") (name "UART2_RXD") (class "Default")
      (node (ref "P9") (pin "22") (pinfunction "1_22") (pintype "passive"))
      (node (ref "X1") (pin "8") (pinfunction "P$8_8") (pintype "bidirectional"))
    )
    (net (code "92") (name "UART2_TXD") (class "Default")
      (node (ref "P9") (pin "21") (pinfunction "1_21") (pintype "passive"))
      (node (ref "X1") (pin "10") (pinfunction "P$10_10") (pintype "bidirectional"))
    )
    (net (code "93") (name "UART4_CTSN") (class "Default")
      (node (ref "P8") (pin "35") (pinfunction "1_35") (pintype "passive"))
    )
    (net (code "94") (name "UART4_RTSN") (class "Default")
      (node (ref "P8") (pin "33") (pinfunction "1_33") (pintype "passive"))
    )
    (net (code "95") (name "UART5_RXD") (class "Default")
      (node (ref "P8") (pin "38") (pinfunction "1_38") (pintype "passive"))
      (node (ref "U6") (pin "44") (pinfunction "GPS_TXD0_44") (pintype "output"))
      (node (ref "U7") (pin "4") (pinfunction "RX_4") (pintype "bidirectional"))
    )
    (net (code "96") (name "UART5_TXD") (class "Default")
      (node (ref "P8") (pin "37") (pinfunction "1_37") (pintype "passive"))
      (node (ref "U6") (pin "42") (pinfunction "GPS_RXDO_42") (pintype "input"))
      (node (ref "U7") (pin "5") (pinfunction "TX_5") (pintype "bidirectional"))
    )
    (net (code "97") (name "unconnected-(H1-Pad1.9)") (class "Default")
      (node (ref "H1") (pin "1.9") (pinfunction "1.9_1.9") (pintype "bidirectional"))
    )
    (net (code "98") (name "unconnected-(H1-Pad1.10)") (class "Default")
      (node (ref "H1") (pin "1.10") (pinfunction "1.10_1.10") (pintype "bidirectional"))
    )
    (net (code "99") (name "unconnected-(H1-Pad1.11)") (class "Default")
      (node (ref "H1") (pin "1.11") (pinfunction "1.11_1.11") (pintype "bidirectional"))
    )
    (net (code "100") (name "unconnected-(H1-Pad1.12)") (class "Default")
      (node (ref "H1") (pin "1.12") (pinfunction "1.12_1.12") (pintype "bidirectional"))
    )
    (net (code "101") (name "unconnected-(H1-Pad1.13)") (class "Default")
      (node (ref "H1") (pin "1.13") (pinfunction "1.13_1.13") (pintype "bidirectional"))
    )
    (net (code "102") (name "unconnected-(H1-Pad1.14)") (class "Default")
      (node (ref "H1") (pin "1.14") (pinfunction "1.14_1.14") (pintype "bidirectional"))
    )
    (net (code "103") (name "unconnected-(H1-Pad1.15)") (class "Default")
      (node (ref "H1") (pin "1.15") (pinfunction "1.15_1.15") (pintype "bidirectional"))
    )
    (net (code "104") (name "unconnected-(H1-Pad1.16)") (class "Default")
      (node (ref "H1") (pin "1.16") (pinfunction "1.16_1.16") (pintype "bidirectional"))
    )
    (net (code "105") (name "unconnected-(H1-Pad1.17)") (class "Default")
      (node (ref "H1") (pin "1.17") (pinfunction "1.17_1.17") (pintype "bidirectional"))
    )
    (net (code "106") (name "unconnected-(H1-Pad1.18)") (class "Default")
      (node (ref "H1") (pin "1.18") (pinfunction "1.18_1.18") (pintype "bidirectional"))
    )
    (net (code "107") (name "unconnected-(H1-Pad1.19)") (class "Default")
      (node (ref "H1") (pin "1.19") (pinfunction "1.19_1.19") (pintype "bidirectional"))
    )
    (net (code "108") (name "unconnected-(H1-Pad1.20)") (class "Default")
      (node (ref "H1") (pin "1.20") (pinfunction "1.20_1.20") (pintype "bidirectional"))
    )
    (net (code "109") (name "unconnected-(H1-Pad1.21)") (class "Default")
      (node (ref "H1") (pin "1.21") (pinfunction "1.21_1.21") (pintype "bidirectional"))
    )
    (net (code "110") (name "unconnected-(H1-Pad1.22)") (class "Default")
      (node (ref "H1") (pin "1.22") (pinfunction "1.22_1.22") (pintype "bidirectional"))
    )
    (net (code "111") (name "unconnected-(H1-Pad1.23)") (class "Default")
      (node (ref "H1") (pin "1.23") (pinfunction "1.23_1.23") (pintype "bidirectional"))
    )
    (net (code "112") (name "unconnected-(H1-Pad1.24)") (class "Default")
      (node (ref "H1") (pin "1.24") (pinfunction "1.24_1.24") (pintype "bidirectional"))
    )
    (net (code "113") (name "unconnected-(H1-Pad1.25)") (class "Default")
      (node (ref "H1") (pin "1.25") (pinfunction "1.25_1.25") (pintype "bidirectional"))
    )
    (net (code "114") (name "unconnected-(H1-Pad1.26)") (class "Default")
      (node (ref "H1") (pin "1.26") (pinfunction "1.26_1.26") (pintype "bidirectional"))
    )
    (net (code "115") (name "unconnected-(H1-Pad1.27)") (class "Default")
      (node (ref "H1") (pin "1.27") (pinfunction "1.27_1.27") (pintype "bidirectional"))
    )
    (net (code "116") (name "unconnected-(H1-Pad1.28)") (class "Default")
      (node (ref "H1") (pin "1.28") (pinfunction "1.28_1.28") (pintype "bidirectional"))
    )
    (net (code "117") (name "unconnected-(H1-Pad1.29)") (class "Default")
      (node (ref "H1") (pin "1.29") (pinfunction "1.29_1.29") (pintype "bidirectional"))
    )
    (net (code "118") (name "unconnected-(H1-Pad1.30)") (class "Default")
      (node (ref "H1") (pin "1.30") (pinfunction "1.30_1.30") (pintype "bidirectional"))
    )
    (net (code "119") (name "unconnected-(H1-Pad1.31)") (class "Default")
      (node (ref "H1") (pin "1.31") (pinfunction "1.31_1.31") (pintype "bidirectional"))
    )
    (net (code "120") (name "unconnected-(H1-Pad1.32)") (class "Default")
      (node (ref "H1") (pin "1.32") (pinfunction "1.32_1.32") (pintype "bidirectional"))
    )
    (net (code "121") (name "unconnected-(H1-Pad1.33)") (class "Default")
      (node (ref "H1") (pin "1.33") (pinfunction "1.33_1.33") (pintype "bidirectional"))
    )
    (net (code "122") (name "unconnected-(H1-Pad1.34)") (class "Default")
      (node (ref "H1") (pin "1.34") (pinfunction "1.34_1.34") (pintype "bidirectional"))
    )
    (net (code "123") (name "unconnected-(H1-Pad1.35)") (class "Default")
      (node (ref "H1") (pin "1.35") (pinfunction "1.35_1.35") (pintype "bidirectional"))
    )
    (net (code "124") (name "unconnected-(H1-Pad1.36)") (class "Default")
      (node (ref "H1") (pin "1.36") (pinfunction "1.36_1.36") (pintype "bidirectional"))
    )
    (net (code "125") (name "unconnected-(H1-Pad1.37)") (class "Default")
      (node (ref "H1") (pin "1.37") (pinfunction "1.37_1.37") (pintype "bidirectional"))
    )
    (net (code "126") (name "unconnected-(H1-Pad1.38)") (class "Default")
      (node (ref "H1") (pin "1.38") (pinfunction "1.38_1.38") (pintype "bidirectional"))
    )
    (net (code "127") (name "unconnected-(H1-Pad1.39)") (class "Default")
      (node (ref "H1") (pin "1.39") (pinfunction "1.39_1.39") (pintype "bidirectional"))
    )
    (net (code "128") (name "unconnected-(H1-Pad1.40)") (class "Default")
      (node (ref "H1") (pin "1.40") (pinfunction "1.40_1.40") (pintype "bidirectional"))
    )
    (net (code "129") (name "unconnected-(H1-Pad1.41)") (class "Default")
      (node (ref "H1") (pin "1.41") (pinfunction "1.41_1.41") (pintype "bidirectional"))
    )
    (net (code "130") (name "unconnected-(H1-Pad1.42)") (class "Default")
      (node (ref "H1") (pin "1.42") (pinfunction "1.42_1.42") (pintype "bidirectional"))
    )
    (net (code "131") (name "unconnected-(H1-Pad1.43)") (class "Default")
      (node (ref "H1") (pin "1.43") (pinfunction "1.43_1.43") (pintype "bidirectional"))
    )
    (net (code "132") (name "unconnected-(H1-Pad1.44)") (class "Default")
      (node (ref "H1") (pin "1.44") (pinfunction "1.44_1.44") (pintype "bidirectional"))
    )
    (net (code "133") (name "unconnected-(H1-Pad1.45)") (class "Default")
      (node (ref "H1") (pin "1.45") (pinfunction "1.45_1.45") (pintype "bidirectional"))
    )
    (net (code "134") (name "unconnected-(H1-Pad1.46)") (class "Default")
      (node (ref "H1") (pin "1.46") (pinfunction "1.46_1.46") (pintype "bidirectional"))
    )
    (net (code "135") (name "unconnected-(H1-Pad1.47)") (class "Default")
      (node (ref "H1") (pin "1.47") (pinfunction "1.47_1.47") (pintype "bidirectional"))
    )
    (net (code "136") (name "unconnected-(H1-Pad1.48)") (class "Default")
      (node (ref "H1") (pin "1.48") (pinfunction "1.48_1.48") (pintype "bidirectional"))
    )
    (net (code "137") (name "unconnected-(H1-Pad1.49)") (class "Default")
      (node (ref "H1") (pin "1.49") (pinfunction "1.49_1.49") (pintype "bidirectional"))
    )
    (net (code "138") (name "unconnected-(H1-Pad1.50)") (class "Default")
      (node (ref "H1") (pin "1.50") (pinfunction "1.50_1.50") (pintype "bidirectional"))
    )
    (net (code "139") (name "unconnected-(H1-Pad1.51)") (class "Default")
      (node (ref "H1") (pin "1.51") (pinfunction "1.51_1.51") (pintype "bidirectional"))
    )
    (net (code "140") (name "unconnected-(H1-Pad1.52)") (class "Default")
      (node (ref "H1") (pin "1.52") (pinfunction "1.52_1.52") (pintype "bidirectional"))
    )
    (net (code "141") (name "unconnected-(H1-Pad2.1)") (class "Default")
      (node (ref "H1") (pin "2.1") (pinfunction "2.1_2.1") (pintype "bidirectional"))
    )
    (net (code "142") (name "unconnected-(H1-Pad2.2)") (class "Default")
      (node (ref "H1") (pin "2.2") (pinfunction "2.2_2.2") (pintype "bidirectional"))
    )
    (net (code "143") (name "unconnected-(H1-Pad2.3)") (class "Default")
      (node (ref "H1") (pin "2.3") (pinfunction "2.3_2.3") (pintype "bidirectional"))
    )
    (net (code "144") (name "unconnected-(H1-Pad2.4)") (class "Default")
      (node (ref "H1") (pin "2.4") (pinfunction "2.4_2.4") (pintype "bidirectional"))
    )
    (net (code "145") (name "unconnected-(H1-Pad2.5)") (class "Default")
      (node (ref "H1") (pin "2.5") (pinfunction "2.5_2.5") (pintype "bidirectional"))
    )
    (net (code "146") (name "unconnected-(H1-Pad2.6)") (class "Default")
      (node (ref "H1") (pin "2.6") (pinfunction "2.6_2.6") (pintype "bidirectional"))
    )
    (net (code "147") (name "unconnected-(H1-Pad2.8)") (class "Default")
      (node (ref "H1") (pin "2.8") (pinfunction "2.8_2.8") (pintype "bidirectional"))
    )
    (net (code "148") (name "unconnected-(H1-Pad2.9)") (class "Default")
      (node (ref "H1") (pin "2.9") (pinfunction "2.9_2.9") (pintype "bidirectional"))
    )
    (net (code "149") (name "unconnected-(H1-Pad2.10)") (class "Default")
      (node (ref "H1") (pin "2.10") (pinfunction "2.10_2.10") (pintype "bidirectional"))
    )
    (net (code "150") (name "unconnected-(H1-Pad2.11)") (class "Default")
      (node (ref "H1") (pin "2.11") (pinfunction "2.11_2.11") (pintype "bidirectional"))
    )
    (net (code "151") (name "unconnected-(H1-Pad2.12)") (class "Default")
      (node (ref "H1") (pin "2.12") (pinfunction "2.12_2.12") (pintype "bidirectional"))
    )
    (net (code "152") (name "unconnected-(H1-Pad2.15)") (class "Default")
      (node (ref "H1") (pin "2.15") (pinfunction "2.15_2.15") (pintype "bidirectional"))
    )
    (net (code "153") (name "unconnected-(H1-Pad2.16)") (class "Default")
      (node (ref "H1") (pin "2.16") (pinfunction "2.16_2.16") (pintype "bidirectional"))
    )
    (net (code "154") (name "unconnected-(H1-Pad2.18)") (class "Default")
      (node (ref "H1") (pin "2.18") (pinfunction "2.18_2.18") (pintype "bidirectional"))
    )
    (net (code "155") (name "unconnected-(H1-Pad2.19)") (class "Default")
      (node (ref "H1") (pin "2.19") (pinfunction "2.19_2.19") (pintype "bidirectional"))
    )
    (net (code "156") (name "unconnected-(H1-Pad2.20)") (class "Default")
      (node (ref "H1") (pin "2.20") (pinfunction "2.20_2.20") (pintype "bidirectional"))
    )
    (net (code "157") (name "unconnected-(H1-Pad2.23)") (class "Default")
      (node (ref "H1") (pin "2.23") (pinfunction "2.23_2.23") (pintype "bidirectional"))
    )
    (net (code "158") (name "unconnected-(H1-Pad2.24)") (class "Default")
      (node (ref "H1") (pin "2.24") (pinfunction "2.24_2.24") (pintype "bidirectional"))
    )
    (net (code "159") (name "unconnected-(H1-Pad2.31)") (class "Default")
      (node (ref "H1") (pin "2.31") (pinfunction "2.31_2.31") (pintype "bidirectional"))
    )
    (net (code "160") (name "unconnected-(H1-Pad2.33)") (class "Default")
      (node (ref "H1") (pin "2.33") (pinfunction "2.33_2.33") (pintype "bidirectional"))
    )
    (net (code "161") (name "unconnected-(H1-Pad2.34)") (class "Default")
      (node (ref "H1") (pin "2.34") (pinfunction "2.34_2.34") (pintype "bidirectional"))
    )
    (net (code "162") (name "unconnected-(H1-Pad2.35)") (class "Default")
      (node (ref "H1") (pin "2.35") (pinfunction "2.35_2.35") (pintype "bidirectional"))
    )
    (net (code "163") (name "unconnected-(H1-Pad2.36)") (class "Default")
      (node (ref "H1") (pin "2.36") (pinfunction "2.36_2.36") (pintype "bidirectional"))
    )
    (net (code "164") (name "unconnected-(H1-Pad2.37)") (class "Default")
      (node (ref "H1") (pin "2.37") (pinfunction "2.37_2.37") (pintype "bidirectional"))
    )
    (net (code "165") (name "unconnected-(H1-Pad2.38)") (class "Default")
      (node (ref "H1") (pin "2.38") (pinfunction "2.38_2.38") (pintype "bidirectional"))
    )
    (net (code "166") (name "unconnected-(H1-Pad2.39)") (class "Default")
      (node (ref "H1") (pin "2.39") (pinfunction "2.39_2.39") (pintype "bidirectional"))
    )
    (net (code "167") (name "unconnected-(H1-Pad2.40)") (class "Default")
      (node (ref "H1") (pin "2.40") (pinfunction "2.40_2.40") (pintype "bidirectional"))
    )
    (net (code "168") (name "unconnected-(H1-Pad2.41)") (class "Default")
      (node (ref "H1") (pin "2.41") (pinfunction "2.41_2.41") (pintype "bidirectional"))
    )
    (net (code "169") (name "unconnected-(H1-Pad2.42)") (class "Default")
      (node (ref "H1") (pin "2.42") (pinfunction "2.42_2.42") (pintype "bidirectional"))
    )
    (net (code "170") (name "unconnected-(H1-Pad2.43)") (class "Default")
      (node (ref "H1") (pin "2.43") (pinfunction "2.43_2.43") (pintype "bidirectional"))
    )
    (net (code "171") (name "unconnected-(H1-Pad2.44)") (class "Default")
      (node (ref "H1") (pin "2.44") (pinfunction "2.44_2.44") (pintype "bidirectional"))
    )
    (net (code "172") (name "unconnected-(H1-Pad2.45)") (class "Default")
      (node (ref "H1") (pin "2.45") (pinfunction "2.45_2.45") (pintype "bidirectional"))
    )
    (net (code "173") (name "unconnected-(H1-Pad2.46)") (class "Default")
      (node (ref "H1") (pin "2.46") (pinfunction "2.46_2.46") (pintype "bidirectional"))
    )
    (net (code "174") (name "unconnected-(H1-Pad2.49)") (class "Default")
      (node (ref "H1") (pin "2.49") (pinfunction "2.49_2.49") (pintype "bidirectional"))
    )
    (net (code "175") (name "unconnected-(H1-Pad2.50)") (class "Default")
      (node (ref "H1") (pin "2.50") (pinfunction "2.50_2.50") (pintype "bidirectional"))
    )
    (net (code "176") (name "unconnected-(H1-Pad2.51)") (class "Default")
      (node (ref "H1") (pin "2.51") (pinfunction "2.51_2.51") (pintype "bidirectional"))
    )
    (net (code "177") (name "unconnected-(H1-Pad2.52)") (class "Default")
      (node (ref "H1") (pin "2.52") (pinfunction "2.52_2.52") (pintype "bidirectional"))
    )
    (net (code "178") (name "unconnected-(H1-PadP$1)") (class "Default")
      (node (ref "H1") (pin "P$1") (pinfunction "P$1_P$1") (pintype "bidirectional"))
    )
    (net (code "179") (name "unconnected-(H1-PadP$2)") (class "Default")
      (node (ref "H1") (pin "P$2") (pinfunction "P$2_P$2") (pintype "bidirectional"))
    )
    (net (code "180") (name "unconnected-(H1-PadP$3)") (class "Default")
      (node (ref "H1") (pin "P$3") (pinfunction "P$3_P$3") (pintype "bidirectional"))
    )
    (net (code "181") (name "unconnected-(JP4-Pad1)") (class "Default")
      (node (ref "JP4") (pin "1") (pinfunction "1_1") (pintype "passive"))
    )
    (net (code "182") (name "unconnected-(P8AB-1-Pad34)") (class "Default")
      (node (ref "P8") (pin "34") (pinfunction "1_34") (pintype "passive"))
    )
    (net (code "183") (name "unconnected-(P8AS-1-Pad8)") (class "Default")
      (node (ref "P8") (pin "8") (pinfunction "1_8") (pintype "passive"))
    )
    (net (code "184") (name "unconnected-(P8AT-1-Pad9)") (class "Default")
      (node (ref "P8") (pin "9") (pinfunction "1_9") (pintype "passive"))
    )
    (net (code "185") (name "unconnected-(P8B-1-Pad10)") (class "Default")
      (node (ref "P8") (pin "10") (pinfunction "1_10") (pintype "passive"))
    )
    (net (code "186") (name "unconnected-(P8E-1-Pad13)") (class "Default")
      (node (ref "P8") (pin "13") (pinfunction "1_13") (pintype "passive"))
    )
    (net (code "187") (name "unconnected-(P8F-1-Pad14)") (class "Default")
      (node (ref "P8") (pin "14") (pinfunction "1_14") (pintype "passive"))
    )
    (net (code "188") (name "unconnected-(P8K-1-Pad19)") (class "Default")
      (node (ref "P8") (pin "19") (pinfunction "1_19") (pintype "passive"))
    )
    (net (code "189") (name "unconnected-(P8O-1-Pad22)") (class "Default")
      (node (ref "P8") (pin "22") (pinfunction "1_22") (pintype "passive"))
    )
    (net (code "190") (name "unconnected-(P9AJ-1-Pad41)") (class "Default")
      (node (ref "P9") (pin "41") (pinfunction "1_41") (pintype "passive"))
    )
    (net (code "191") (name "unconnected-(P9AL-1-Pad43)") (class "Default")
      (node (ref "P9") (pin "43") (pinfunction "1_43") (pintype "passive"))
    )
    (net (code "192") (name "unconnected-(P9AM-1-Pad44)") (class "Default")
      (node (ref "P9") (pin "44") (pinfunction "1_44") (pintype "passive"))
    )
    (net (code "193") (name "unconnected-(P9AN-1-Pad45)") (class "Default")
      (node (ref "P9") (pin "45") (pinfunction "1_45") (pintype "passive"))
    )
    (net (code "194") (name "unconnected-(P9AO-1-Pad46)") (class "Default")
      (node (ref "P9") (pin "46") (pinfunction "1_46") (pintype "passive"))
    )
    (net (code "195") (name "unconnected-(P9AR-1-Pad7)") (class "Default")
      (node (ref "P9") (pin "7") (pinfunction "1_7") (pintype "passive"))
    )
    (net (code "196") (name "unconnected-(P9AS-1-Pad8)") (class "Default")
      (node (ref "P9") (pin "8") (pinfunction "1_8") (pintype "passive"))
    )
    (net (code "197") (name "unconnected-(P9AT-1-Pad9)") (class "Default")
      (node (ref "P9") (pin "9") (pinfunction "1_9") (pintype "passive"))
    )
    (net (code "198") (name "unconnected-(P9F-1-Pad14)") (class "Default")
      (node (ref "P9") (pin "14") (pinfunction "1_14") (pintype "passive"))
    )
    (net (code "199") (name "unconnected-(P9H-1-Pad16)") (class "Default")
      (node (ref "P9") (pin "16") (pinfunction "1_16") (pintype "passive"))
    )
    (net (code "200") (name "unconnected-(P9I-1-Pad17)") (class "Default")
      (node (ref "P9") (pin "17") (pinfunction "1_17") (pintype "passive"))
    )
    (net (code "201") (name "unconnected-(P9J-1-Pad18)") (class "Default")
      (node (ref "P9") (pin "18") (pinfunction "1_18") (pintype "passive"))
    )
    (net (code "202") (name "unconnected-(P9Z-1-Pad32)") (class "Default")
      (node (ref "P9") (pin "32") (pinfunction "1_32") (pintype "passive"))
    )
    (net (code "203") (name "unconnected-(U1-NC-Pad7)") (class "Default")
      (node (ref "U1") (pin "7") (pinfunction "NC_7") (pintype "no_connect"))
    )
    (net (code "204") (name "unconnected-(U1-NC_2-Pad2)") (class "Default")
      (node (ref "U1") (pin "2") (pinfunction "NC_2_2") (pintype "no_connect"))
    )
    (net (code "205") (name "unconnected-(U1-NC_3-Pad3)") (class "Default")
      (node (ref "U1") (pin "3") (pinfunction "NC_3_3") (pintype "no_connect"))
    )
    (net (code "206") (name "unconnected-(U1-NC_4-Pad6)") (class "Default")
      (node (ref "U1") (pin "6") (pinfunction "NC_4_6") (pintype "no_connect"))
    )
    (net (code "207") (name "unconnected-(U3-DIO0-Pad10)") (class "Default")
      (node (ref "U3") (pin "10") (pinfunction "DIO0_10") (pintype "bidirectional"))
    )
    (net (code "208") (name "unconnected-(U3-DIO1-Pad11)") (class "Default")
      (node (ref "U3") (pin "11") (pinfunction "DIO1_11") (pintype "bidirectional"))
    )
    (net (code "209") (name "unconnected-(U3-DIO2-Pad12)") (class "Default")
      (node (ref "U3") (pin "12") (pinfunction "DIO2_12") (pintype "bidirectional"))
    )
    (net (code "210") (name "unconnected-(U3-DIO3-Pad13)") (class "Default")
      (node (ref "U3") (pin "13") (pinfunction "DIO3_13") (pintype "bidirectional"))
    )
    (net (code "211") (name "unconnected-(U3-DIO4-Pad14)") (class "Default")
      (node (ref "U3") (pin "14") (pinfunction "DIO4_14") (pintype "bidirectional"))
    )
    (net (code "212") (name "unconnected-(U3-DIO5-Pad15)") (class "Default")
      (node (ref "U3") (pin "15") (pinfunction "DIO5_15") (pintype "bidirectional"))
    )
    (net (code "213") (name "unconnected-(U3-NC-Pad1)") (class "Default")
      (node (ref "U3") (pin "1") (pinfunction "NC_1") (pintype "bidirectional"))
    )
    (net (code "214") (name "unconnected-(U6-P$3-Pad3)") (class "Default")
      (node (ref "U6") (pin "3") (pinfunction "P$3_3") (pintype "bidirectional"))
    )
    (net (code "215") (name "unconnected-(U6-P$4-Pad4)") (class "Default")
      (node (ref "U6") (pin "4") (pinfunction "P$4_4") (pintype "bidirectional"))
    )
    (net (code "216") (name "unconnected-(U6-P$5-Pad5)") (class "Default")
      (node (ref "U6") (pin "5") (pinfunction "P$5_5") (pintype "bidirectional"))
    )
    (net (code "217") (name "unconnected-(U6-P$6-Pad6)") (class "Default")
      (node (ref "U6") (pin "6") (pinfunction "P$6_6") (pintype "bidirectional"))
    )
    (net (code "218") (name "unconnected-(U6-P$8-Pad8)") (class "Default")
      (node (ref "U6") (pin "8") (pinfunction "P$8_8") (pintype "bidirectional"))
    )
    (net (code "219") (name "unconnected-(U6-P$12-Pad12)") (class "Default")
      (node (ref "U6") (pin "12") (pinfunction "P$12_12") (pintype "bidirectional"))
    )
    (net (code "220") (name "unconnected-(U6-P$13-Pad13)") (class "Default")
      (node (ref "U6") (pin "13") (pinfunction "P$13_13") (pintype "bidirectional"))
    )
    (net (code "221") (name "unconnected-(U6-P$14-Pad14)") (class "Default")
      (node (ref "U6") (pin "14") (pinfunction "P$14_14") (pintype "bidirectional"))
    )
    (net (code "222") (name "unconnected-(U6-P$16-Pad16)") (class "Default")
      (node (ref "U6") (pin "16") (pinfunction "P$16_16") (pintype "bidirectional"))
    )
    (net (code "223") (name "unconnected-(U6-P$17-Pad17)") (class "Default")
      (node (ref "U6") (pin "17") (pinfunction "P$17_17") (pintype "bidirectional"))
    )
    (net (code "224") (name "unconnected-(U6-P$20-Pad20)") (class "Default")
      (node (ref "U6") (pin "20") (pinfunction "P$20_20") (pintype "bidirectional"))
    )
    (net (code "225") (name "unconnected-(U6-P$23-Pad23)") (class "Default")
      (node (ref "U6") (pin "23") (pinfunction "P$23_23") (pintype "bidirectional"))
    )
    (net (code "226") (name "unconnected-(U6-P$26-Pad26)") (class "Default")
      (node (ref "U6") (pin "26") (pinfunction "P$26_26") (pintype "bidirectional"))
    )
    (net (code "227") (name "unconnected-(U6-P$30-Pad30)") (class "Default")
      (node (ref "U6") (pin "30") (pinfunction "P$30_30") (pintype "bidirectional"))
    )
    (net (code "228") (name "unconnected-(U6-P$34-Pad34)") (class "Default")
      (node (ref "U6") (pin "34") (pinfunction "P$34_34") (pintype "bidirectional"))
    )
    (net (code "229") (name "unconnected-(U6-P$35-Pad35)") (class "Default")
      (node (ref "U6") (pin "35") (pinfunction "P$35_35") (pintype "bidirectional"))
    )
    (net (code "230") (name "unconnected-(U6-P$36-Pad36)") (class "Default")
      (node (ref "U6") (pin "36") (pinfunction "P$36_36") (pintype "bidirectional"))
    )
    (net (code "231") (name "unconnected-(U6-P$37-Pad37)") (class "Default")
      (node (ref "U6") (pin "37") (pinfunction "P$37_37") (pintype "bidirectional"))
    )
    (net (code "232") (name "unconnected-(U6-P$38-Pad38)") (class "Default")
      (node (ref "U6") (pin "38") (pinfunction "P$38_38") (pintype "bidirectional"))
    )
    (net (code "233") (name "unconnected-(U6-P$39-Pad39)") (class "Default")
      (node (ref "U6") (pin "39") (pinfunction "P$39_39") (pintype "bidirectional"))
    )
    (net (code "234") (name "unconnected-(U6-P$40-Pad40)") (class "Default")
      (node (ref "U6") (pin "40") (pinfunction "P$40_40") (pintype "bidirectional"))
    )
    (net (code "235") (name "unconnected-(U6-P$41-Pad41)") (class "Default")
      (node (ref "U6") (pin "41") (pinfunction "P$41_41") (pintype "bidirectional"))
    )
    (net (code "236") (name "unconnected-(U6-P$43-Pad43)") (class "Default")
      (node (ref "U6") (pin "43") (pinfunction "P$43_43") (pintype "bidirectional"))
    )
    (net (code "237") (name "unconnected-(U6-P$45-Pad45)") (class "Default")
      (node (ref "U6") (pin "45") (pinfunction "P$45_45") (pintype "bidirectional"))
    )
    (net (code "238") (name "unconnected-(U6-P$46-Pad46)") (class "Default")
      (node (ref "U6") (pin "46") (pinfunction "P$46_46") (pintype "bidirectional"))
    )
    (net (code "239") (name "unconnected-(U6-P$47-Pad47)") (class "Default")
      (node (ref "U6") (pin "47") (pinfunction "P$47_47") (pintype "bidirectional"))
    )
    (net (code "240") (name "unconnected-(U6-P$48-Pad48)") (class "Default")
      (node (ref "U6") (pin "48") (pinfunction "P$48_48") (pintype "bidirectional"))
    )
    (net (code "241") (name "unconnected-(U6-P$49-Pad49)") (class "Default")
      (node (ref "U6") (pin "49") (pinfunction "P$49_49") (pintype "bidirectional"))
    )
    (net (code "242") (name "unconnected-(U6-P$50-Pad50)") (class "Default")
      (node (ref "U6") (pin "50") (pinfunction "P$50_50") (pintype "bidirectional"))
    )
    (net (code "243") (name "unconnected-(U6-P$51-Pad51)") (class "Default")
      (node (ref "U6") (pin "51") (pinfunction "P$51_51") (pintype "bidirectional"))
    )
    (net (code "244") (name "unconnected-(U6-P$52-Pad52)") (class "Default")
      (node (ref "U6") (pin "52") (pinfunction "P$52_52") (pintype "bidirectional"))
    )
    (net (code "245") (name "unconnected-(U6-P$53-Pad53)") (class "Default")
      (node (ref "U6") (pin "53") (pinfunction "P$53_53") (pintype "bidirectional"))
    )
    (net (code "246") (name "unconnected-(U6-P$54-Pad54)") (class "Default")
      (node (ref "U6") (pin "54") (pinfunction "P$54_54") (pintype "bidirectional"))
    )
    (net (code "247") (name "unconnected-(U6-P$55-Pad55)") (class "Default")
      (node (ref "U6") (pin "55") (pinfunction "P$55_55") (pintype "bidirectional"))
    )
    (net (code "248") (name "unconnected-(U6-P$56-Pad56)") (class "Default")
      (node (ref "U6") (pin "56") (pinfunction "P$56_56") (pintype "bidirectional"))
    )
    (net (code "249") (name "unconnected-(U6-P$57-Pad57)") (class "Default")
      (node (ref "U6") (pin "57") (pinfunction "P$57_57") (pintype "bidirectional"))
    )
    (net (code "250") (name "unconnected-(U6-P$59-Pad59)") (class "Default")
      (node (ref "U6") (pin "59") (pinfunction "P$59_59") (pintype "bidirectional"))
    )
    (net (code "251") (name "unconnected-(U6-P$60-Pad60)") (class "Default")
      (node (ref "U6") (pin "60") (pinfunction "P$60_60") (pintype "bidirectional"))
    )
    (net (code "252") (name "unconnected-(U6-P$61-Pad61)") (class "Default")
      (node (ref "U6") (pin "61") (pinfunction "P$61_61") (pintype "bidirectional"))
    )
    (net (code "253") (name "unconnected-(U6-P$62-Pad62)") (class "Default")
      (node (ref "U6") (pin "62") (pinfunction "P$62_62") (pintype "bidirectional"))
    )
    (net (code "254") (name "unconnected-(U6-P$63-Pad63)") (class "Default")
      (node (ref "U6") (pin "63") (pinfunction "P$63_63") (pintype "bidirectional"))
    )
    (net (code "255") (name "unconnected-(U6-P$65-Pad65)") (class "Default")
      (node (ref "U6") (pin "65") (pinfunction "P$65_65") (pintype "bidirectional"))
    )
    (net (code "256") (name "unconnected-(U6-P$66-Pad66)") (class "Default")
      (node (ref "U6") (pin "66") (pinfunction "P$66_66") (pintype "bidirectional"))
    )
    (net (code "257") (name "unconnected-(U6-P$67-Pad67)") (class "Default")
      (node (ref "U6") (pin "67") (pinfunction "P$67_67") (pintype "bidirectional"))
    )
    (net (code "258") (name "unconnected-(U6-P$68-Pad68)") (class "Default")
      (node (ref "U6") (pin "68") (pinfunction "P$68_68") (pintype "bidirectional"))
    )
    (net (code "259") (name "unconnected-(U6-P$69-Pad69)") (class "Default")
      (node (ref "U6") (pin "69") (pinfunction "P$69_69") (pintype "bidirectional"))
    )
    (net (code "260") (name "unconnected-(U7-PPS-Pad2)") (class "Default")
      (node (ref "U7") (pin "2") (pinfunction "PPS_2") (pintype "bidirectional"))
    )
    (net (code "261") (name "unconnected-(X1-P$1-Pad1)") (class "Default")
      (node (ref "X1") (pin "1") (pinfunction "P$1_1") (pintype "bidirectional"))
    )
    (net (code "262") (name "unconnected-(X1-P$4-Pad4)") (class "Default")
      (node (ref "X1") (pin "4") (pinfunction "P$4_4") (pintype "bidirectional"))
    )
    (net (code "263") (name "unconnected-(X1-P$6-Pad6)") (class "Default")
      (node (ref "X1") (pin "6") (pinfunction "P$6_6") (pintype "bidirectional"))
    )
    (net (code "264") (name "unconnected-(X1-P$7-Pad7)") (class "Default")
      (node (ref "X1") (pin "7") (pinfunction "P$7_7") (pintype "bidirectional"))
    )
    (net (code "265") (name "unconnected-(X1-P$9-Pad9)") (class "Default")
      (node (ref "X1") (pin "9") (pinfunction "P$9_9") (pintype "bidirectional"))
    )
    (net (code "266") (name "unconnected-(X1-P$12-Pad12)") (class "Default")
      (node (ref "X1") (pin "12") (pinfunction "P$12_12") (pintype "bidirectional"))
    )
    (net (code "267") (name "unconnected-(X1-P$14-Pad14)") (class "Default")
      (node (ref "X1") (pin "14") (pinfunction "P$14_14") (pintype "bidirectional"))
    )
    (net (code "268") (name "unconnected-(X1-P$17-Pad17)") (class "Default")
      (node (ref "X1") (pin "17") (pinfunction "P$17_17") (pintype "bidirectional"))
    )
    (net (code "269") (name "unconnected-(X1-P$20-Pad20)") (class "Default")
      (node (ref "X1") (pin "20") (pinfunction "P$20_20") (pintype "bidirectional"))
    )
    (net (code "270") (name "unconnected-(X1-P$25-Pad25)") (class "Default")
      (node (ref "X1") (pin "25") (pinfunction "P$25_25") (pintype "bidirectional"))
    )
    (net (code "271") (name "unconnected-(X1-P$27-Pad27)") (class "Default")
      (node (ref "X1") (pin "27") (pinfunction "P$27_27") (pintype "bidirectional"))
    )
    (net (code "272") (name "unconnected-(X1-P$28-Pad28)") (class "Default")
      (node (ref "X1") (pin "28") (pinfunction "P$28_28") (pintype "bidirectional"))
    )
    (net (code "273") (name "unconnected-(X1-P$29-Pad29)") (class "Default")
      (node (ref "X1") (pin "29") (pinfunction "P$29_29") (pintype "bidirectional"))
    )
    (net (code "274") (name "unconnected-(X1-P$30-Pad30)") (class "Default")
      (node (ref "X1") (pin "30") (pinfunction "P$30_30") (pintype "bidirectional"))
    )
    (net (code "275") (name "unconnected-(X1-P$31-Pad31)") (class "Default")
      (node (ref "X1") (pin "31") (pinfunction "P$31_31") (pintype "bidirectional"))
    )
    (net (code "276") (name "unconnected-(X1-P$32-Pad32)") (class "Default")
      (node (ref "X1") (pin "32") (pinfunction "P$32_32") (pintype "bidirectional"))
    )
    (net (code "277") (name "unconnected-(X1-P$33-Pad33)") (class "Default")
      (node (ref "X1") (pin "33") (pinfunction "P$33_33") (pintype "bidirectional"))
    )
    (net (code "278") (name "unconnected-(X1-P$34-Pad34)") (class "Default")
      (node (ref "X1") (pin "34") (pinfunction "P$34_34") (pintype "bidirectional"))
    )
    (net (code "279") (name "unconnected-(X1-P$35-Pad35)") (class "Default")
      (node (ref "X1") (pin "35") (pinfunction "P$35_35") (pintype "bidirectional"))
    )
    (net (code "280") (name "unconnected-(X1-P$36-Pad36)") (class "Default")
      (node (ref "X1") (pin "36") (pinfunction "P$36_36") (pintype "bidirectional"))
    )
    (net (code "281") (name "unconnected-(X1-P$37-Pad37)") (class "Default")
      (node (ref "X1") (pin "37") (pinfunction "P$37_37") (pintype "bidirectional"))
    )
    (net (code "282") (name "unconnected-(X1-P$38-Pad38)") (class "Default")
      (node (ref "X1") (pin "38") (pinfunction "P$38_38") (pintype "bidirectional"))
    )
    (net (code "283") (name "unconnected-(X1-P$40-Pad40)") (class "Default")
      (node (ref "X1") (pin "40") (pinfunction "P$40_40") (pintype "bidirectional"))
    )
    (net (code "284") (name "unconnected-(X2-Pad1)") (class "Default")
      (node (ref "X2") (pin "1") (pinfunction "1_1") (pintype "passive"))
    )
    (net (code "285") (name "unconnected-(X2AA-1-Pad33)") (class "Default")
      (node (ref "X2") (pin "33") (pinfunction "1_33") (pintype "passive"))
    )
    (net (code "286") (name "unconnected-(X2AB-1-Pad34)") (class "Default")
      (node (ref "X2") (pin "34") (pinfunction "1_34") (pintype "passive"))
    )
    (net (code "287") (name "unconnected-(X2AC-1-Pad35)") (class "Default")
      (node (ref "X2") (pin "35") (pinfunction "1_35") (pintype "passive"))
    )
    (net (code "288") (name "unconnected-(X2AD-1-Pad36)") (class "Default")
      (node (ref "X2") (pin "36") (pinfunction "1_36") (pintype "passive"))
    )
    (net (code "289") (name "unconnected-(X2AE-1-Pad37)") (class "Default")
      (node (ref "X2") (pin "37") (pinfunction "1_37") (pintype "passive"))
    )
    (net (code "290") (name "unconnected-(X2AF-1-Pad38)") (class "Default")
      (node (ref "X2") (pin "38") (pinfunction "1_38") (pintype "passive"))
    )
    (net (code "291") (name "unconnected-(X2AG-1-Pad39)") (class "Default")
      (node (ref "X2") (pin "39") (pinfunction "1_39") (pintype "passive"))
    )
    (net (code "292") (name "unconnected-(X2AH-1-Pad4)") (class "Default")
      (node (ref "X2") (pin "4") (pinfunction "1_4") (pintype "passive"))
    )
    (net (code "293") (name "unconnected-(X2AI-1-Pad40)") (class "Default")
      (node (ref "X2") (pin "40") (pinfunction "1_40") (pintype "passive"))
    )
    (net (code "294") (name "unconnected-(X2AJ-1-Pad5)") (class "Default")
      (node (ref "X2") (pin "5") (pinfunction "1_5") (pintype "passive"))
    )
    (net (code "295") (name "unconnected-(X2AK-1-Pad6)") (class "Default")
      (node (ref "X2") (pin "6") (pinfunction "1_6") (pintype "passive"))
    )
    (net (code "296") (name "unconnected-(X2AL-1-Pad7)") (class "Default")
      (node (ref "X2") (pin "7") (pinfunction "1_7") (pintype "passive"))
    )
    (net (code "297") (name "unconnected-(X2AM-1-Pad8)") (class "Default")
      (node (ref "X2") (pin "8") (pinfunction "1_8") (pintype "passive"))
    )
    (net (code "298") (name "unconnected-(X2AN-1-Pad9)") (class "Default")
      (node (ref "X2") (pin "9") (pinfunction "1_9") (pintype "passive"))
    )
    (net (code "299") (name "unconnected-(X2B-1-Pad10)") (class "Default")
      (node (ref "X2") (pin "10") (pinfunction "1_10") (pintype "passive"))
    )
    (net (code "300") (name "unconnected-(X2C-1-Pad11)") (class "Default")
      (node (ref "X2") (pin "11") (pinfunction "1_11") (pintype "passive"))
    )
    (net (code "301") (name "unconnected-(X2D-1-Pad12)") (class "Default")
      (node (ref "X2") (pin "12") (pinfunction "1_12") (pintype "passive"))
    )
    (net (code "302") (name "unconnected-(X2E-1-Pad13)") (class "Default")
      (node (ref "X2") (pin "13") (pinfunction "1_13") (pintype "passive"))
    )
    (net (code "303") (name "unconnected-(X2F-1-Pad14)") (class "Default")
      (node (ref "X2") (pin "14") (pinfunction "1_14") (pintype "passive"))
    )
    (net (code "304") (name "unconnected-(X2G-1-Pad15)") (class "Default")
      (node (ref "X2") (pin "15") (pinfunction "1_15") (pintype "passive"))
    )
    (net (code "305") (name "unconnected-(X2H-1-Pad16)") (class "Default")
      (node (ref "X2") (pin "16") (pinfunction "1_16") (pintype "passive"))
    )
    (net (code "306") (name "unconnected-(X2I-1-Pad17)") (class "Default")
      (node (ref "X2") (pin "17") (pinfunction "1_17") (pintype "passive"))
    )
    (net (code "307") (name "unconnected-(X2J-1-Pad18)") (class "Default")
      (node (ref "X2") (pin "18") (pinfunction "1_18") (pintype "passive"))
    )
    (net (code "308") (name "unconnected-(X2K-1-Pad19)") (class "Default")
      (node (ref "X2") (pin "19") (pinfunction "1_19") (pintype "passive"))
    )
    (net (code "309") (name "unconnected-(X2L-1-Pad2)") (class "Default")
      (node (ref "X2") (pin "2") (pinfunction "1_2") (pintype "passive"))
    )
    (net (code "310") (name "unconnected-(X2M-1-Pad20)") (class "Default")
      (node (ref "X2") (pin "20") (pinfunction "1_20") (pintype "passive"))
    )
    (net (code "311") (name "unconnected-(X2N-1-Pad21)") (class "Default")
      (node (ref "X2") (pin "21") (pinfunction "1_21") (pintype "passive"))
    )
    (net (code "312") (name "unconnected-(X2O-1-Pad22)") (class "Default")
      (node (ref "X2") (pin "22") (pinfunction "1_22") (pintype "passive"))
    )
    (net (code "313") (name "unconnected-(X2P-1-Pad23)") (class "Default")
      (node (ref "X2") (pin "23") (pinfunction "1_23") (pintype "passive"))
    )
    (net (code "314") (name "unconnected-(X2Q-1-Pad24)") (class "Default")
      (node (ref "X2") (pin "24") (pinfunction "1_24") (pintype "passive"))
    )
    (net (code "315") (name "unconnected-(X2R-1-Pad25)") (class "Default")
      (node (ref "X2") (pin "25") (pinfunction "1_25") (pintype "passive"))
    )
    (net (code "316") (name "unconnected-(X2S-1-Pad26)") (class "Default")
      (node (ref "X2") (pin "26") (pinfunction "1_26") (pintype "passive"))
    )
    (net (code "317") (name "unconnected-(X2T-1-Pad27)") (class "Default")
      (node (ref "X2") (pin "27") (pinfunction "1_27") (pintype "passive"))
    )
    (net (code "318") (name "unconnected-(X2U-1-Pad28)") (class "Default")
      (node (ref "X2") (pin "28") (pinfunction "1_28") (pintype "passive"))
    )
    (net (code "319") (name "unconnected-(X2V-1-Pad29)") (class "Default")
      (node (ref "X2") (pin "29") (pinfunction "1_29") (pintype "passive"))
    )
    (net (code "320") (name "unconnected-(X2W-1-Pad3)") (class "Default")
      (node (ref "X2") (pin "3") (pinfunction "1_3") (pintype "passive"))
    )
    (net (code "321") (name "unconnected-(X2X-1-Pad30)") (class "Default")
      (node (ref "X2") (pin "30") (pinfunction "1_30") (pintype "passive"))
    )
    (net (code "322") (name "unconnected-(X2Y-1-Pad31)") (class "Default")
      (node (ref "X2") (pin "31") (pinfunction "1_31") (pintype "passive"))
    )
    (net (code "323") (name "unconnected-(X2Z-1-Pad32)") (class "Default")
      (node (ref "X2") (pin "32") (pinfunction "1_32") (pintype "passive"))
    )
  )
)
